# Lights.net
KiCad netlist of a schematic drawn in Altium Designer
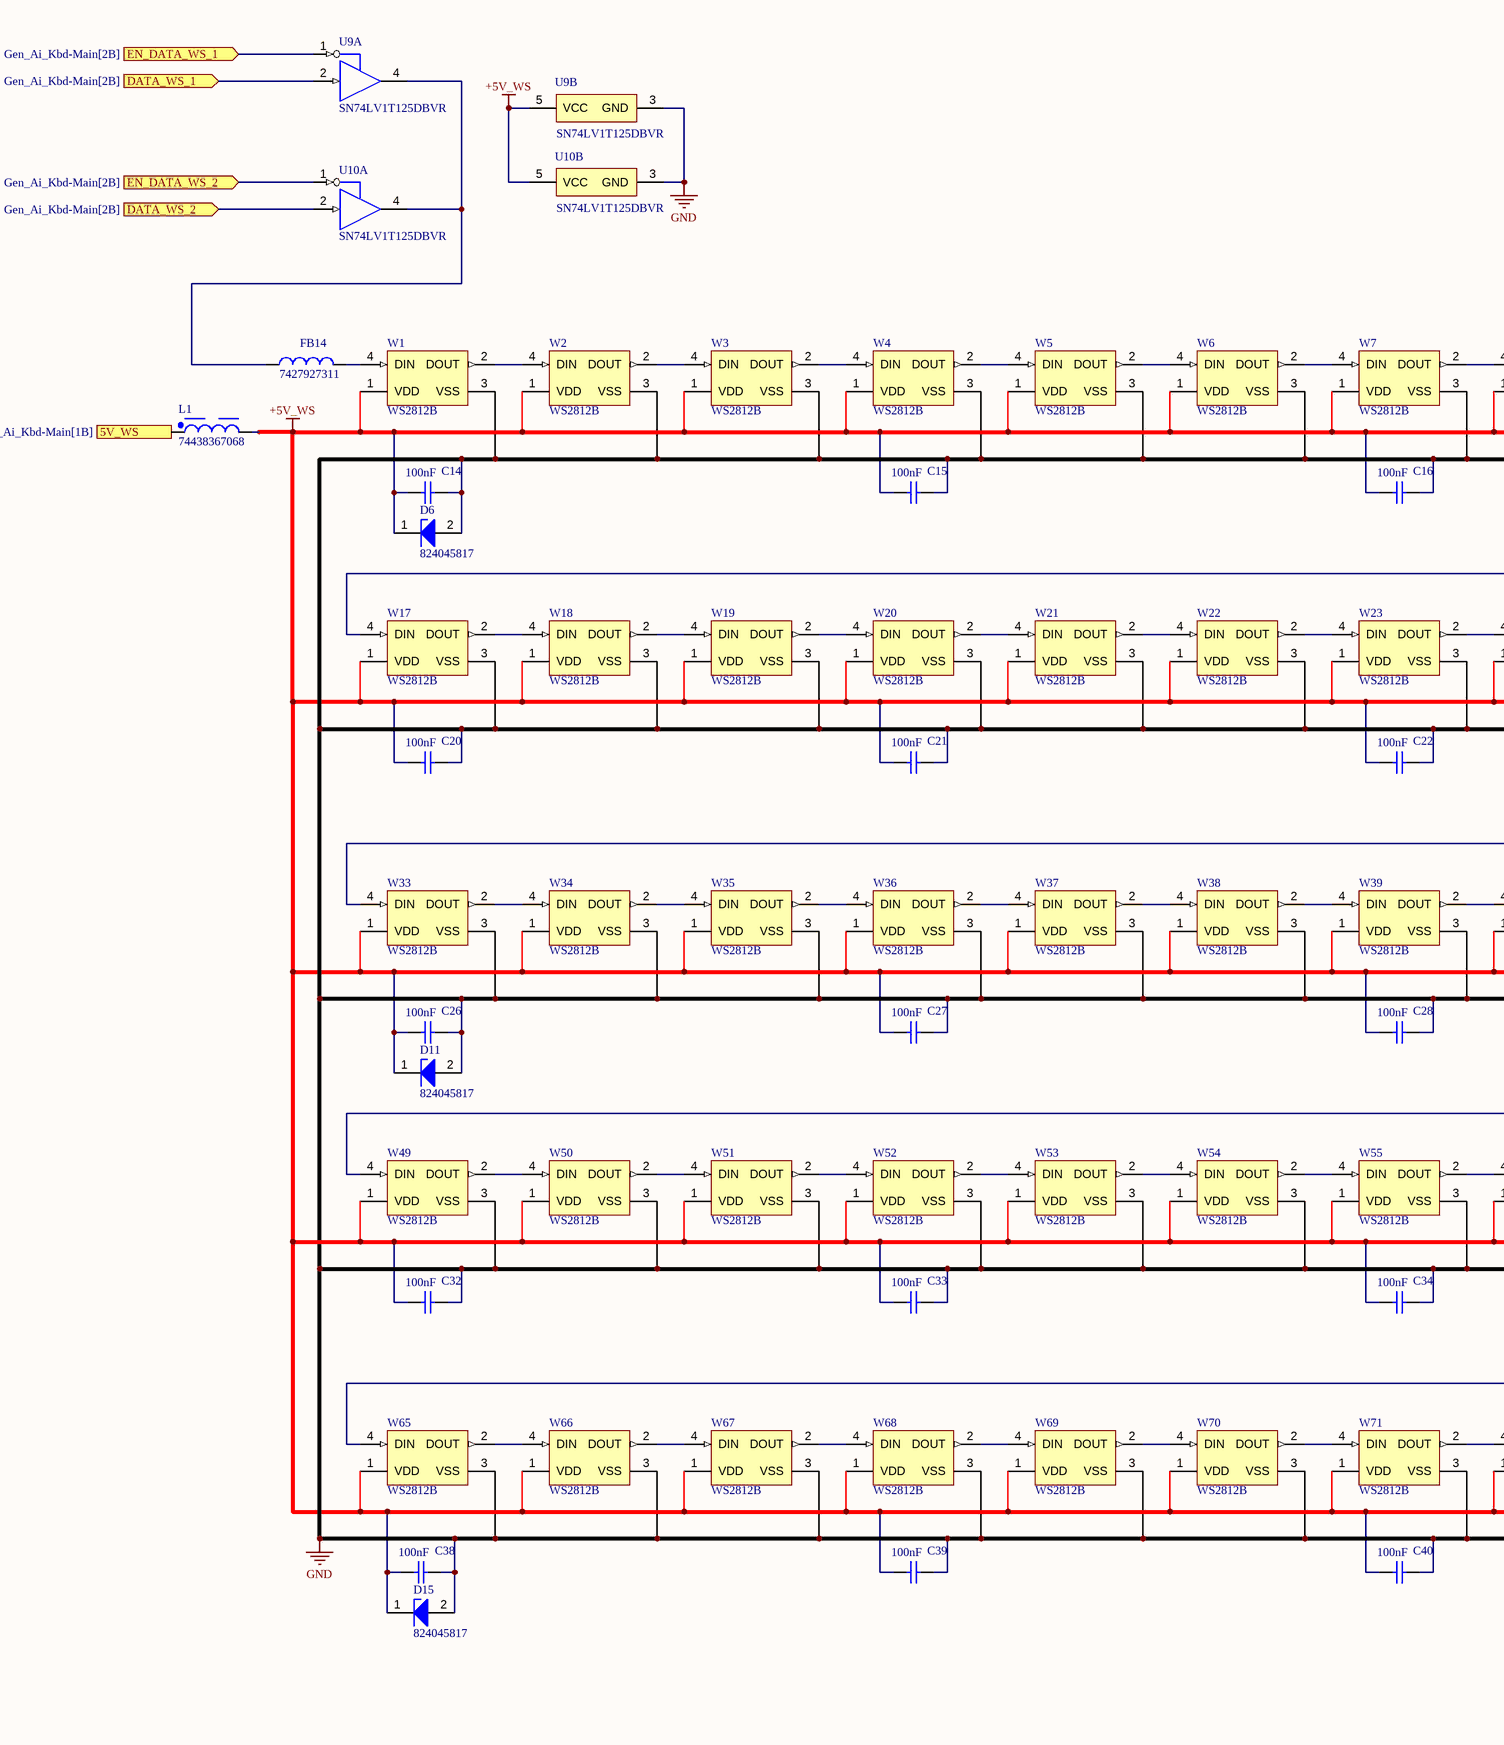
[diagram p0: Lights.SchDoc, left]
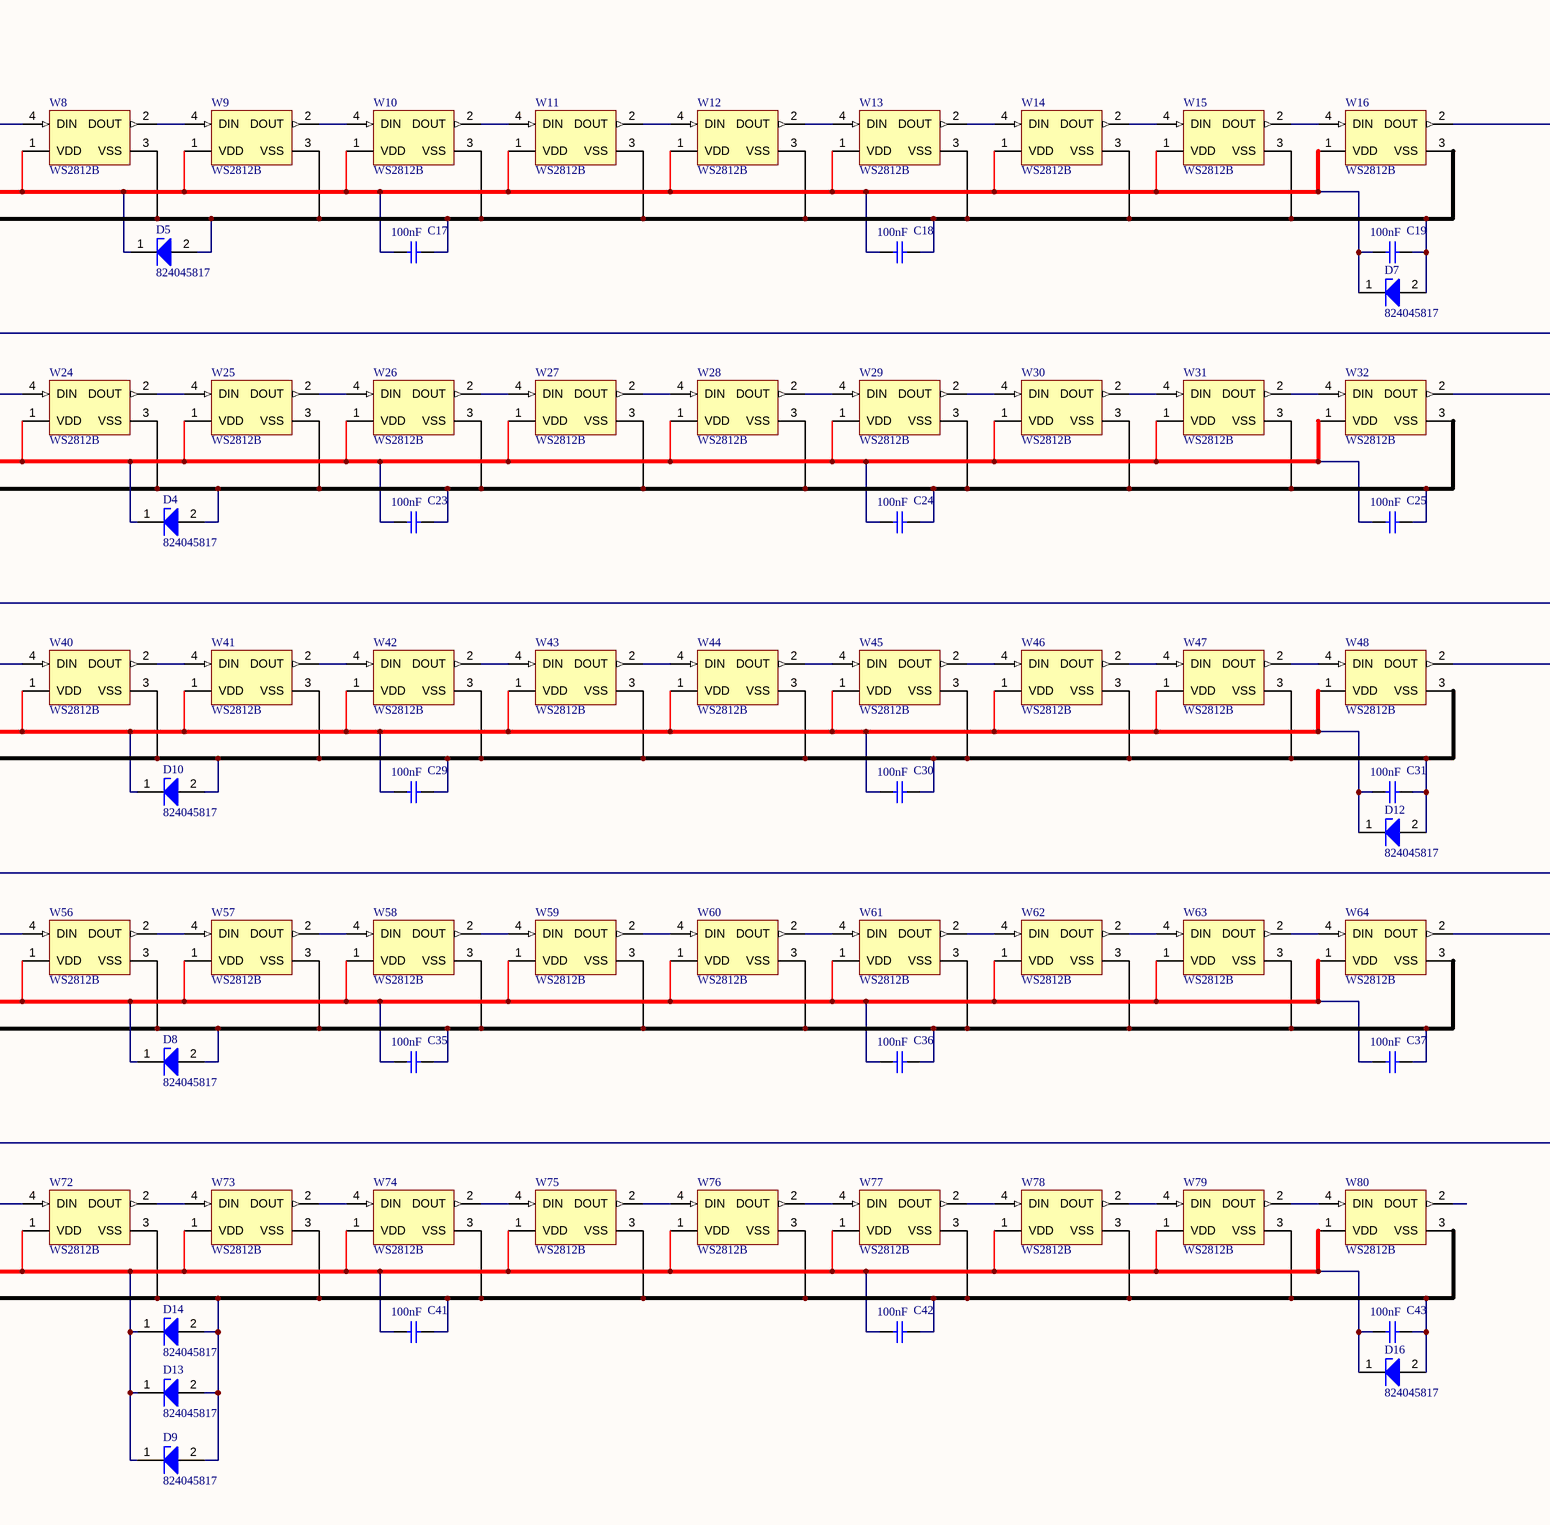
[diagram p1: Lights.SchDoc, right]

(export (version "E")
  (design (tool "Eeschema 10.0.6"))
  (components
    (comp (ref "C14")
      (value "885012205018")
      (footprint "WCAP-CSGP_0402_L1W0.5H0.5")
      (description "WCAP-CSGP Multilayer Ceramic Chip Capacitor, General Purpose, size 0402, X7R, 100nF, 10VDC")
      (fields (field (name "CAPACITANCE") "100nF") (field (name "MANUFACTURER") "Wurth Elektronik"))
      (libsource (lib "Test365") (part "885012209047R"))
    )
    (comp (ref "C15")
      (value "885012205018")
      (footprint "WCAP-CSGP_0402_L1W0.5H0.5")
      (description "WCAP-CSGP Multilayer Ceramic Chip Capacitor, General Purpose, size 0402, X7R, 100nF, 10VDC")
      (fields (field (name "CAPACITANCE") "100nF") (field (name "MANUFACTURER") "Wurth Elektronik"))
      (libsource (lib "Test365") (part "885012209047R"))
    )
    (comp (ref "C16")
      (value "885012205018")
      (footprint "WCAP-CSGP_0402_L1W0.5H0.5")
      (description "WCAP-CSGP Multilayer Ceramic Chip Capacitor, General Purpose, size 0402, X7R, 100nF, 10VDC")
      (fields (field (name "CAPACITANCE") "100nF") (field (name "MANUFACTURER") "Wurth Elektronik"))
      (libsource (lib "Test365") (part "885012209047R"))
    )
    (comp (ref "C17")
      (value "885012205018")
      (footprint "WCAP-CSGP_0402_L1W0.5H0.5")
      (description "WCAP-CSGP Multilayer Ceramic Chip Capacitor, General Purpose, size 0402, X7R, 100nF, 10VDC")
      (fields (field (name "CAPACITANCE") "100nF") (field (name "MANUFACTURER") "Wurth Elektronik"))
      (libsource (lib "Test365") (part "885012209047R"))
    )
    (comp (ref "C18")
      (value "885012205018")
      (footprint "WCAP-CSGP_0402_L1W0.5H0.5")
      (description "WCAP-CSGP Multilayer Ceramic Chip Capacitor, General Purpose, size 0402, X7R, 100nF, 10VDC")
      (fields (field (name "CAPACITANCE") "100nF") (field (name "MANUFACTURER") "Wurth Elektronik"))
      (libsource (lib "Test365") (part "885012209047R"))
    )
    (comp (ref "C19")
      (value "885012205018")
      (footprint "WCAP-CSGP_0402_L1W0.5H0.5")
      (description "WCAP-CSGP Multilayer Ceramic Chip Capacitor, General Purpose, size 0402, X7R, 100nF, 10VDC")
      (fields (field (name "CAPACITANCE") "100nF") (field (name "MANUFACTURER") "Wurth Elektronik"))
      (libsource (lib "Test365") (part "885012209047R"))
    )
    (comp (ref "C20")
      (value "885012205018")
      (footprint "WCAP-CSGP_0402_L1W0.5H0.5")
      (description "WCAP-CSGP Multilayer Ceramic Chip Capacitor, General Purpose, size 0402, X7R, 100nF, 10VDC")
      (fields (field (name "CAPACITANCE") "100nF") (field (name "MANUFACTURER") "Wurth Elektronik"))
      (libsource (lib "Test365") (part "885012209047R"))
    )
    (comp (ref "C21")
      (value "885012205018")
      (footprint "WCAP-CSGP_0402_L1W0.5H0.5")
      (description "WCAP-CSGP Multilayer Ceramic Chip Capacitor, General Purpose, size 0402, X7R, 100nF, 10VDC")
      (fields (field (name "CAPACITANCE") "100nF") (field (name "MANUFACTURER") "Wurth Elektronik"))
      (libsource (lib "Test365") (part "885012209047R"))
    )
    (comp (ref "C22")
      (value "885012205018")
      (footprint "WCAP-CSGP_0402_L1W0.5H0.5")
      (description "WCAP-CSGP Multilayer Ceramic Chip Capacitor, General Purpose, size 0402, X7R, 100nF, 10VDC")
      (fields (field (name "CAPACITANCE") "100nF") (field (name "MANUFACTURER") "Wurth Elektronik"))
      (libsource (lib "Test365") (part "885012209047R"))
    )
    (comp (ref "C23")
      (value "885012205018")
      (footprint "WCAP-CSGP_0402_L1W0.5H0.5")
      (description "WCAP-CSGP Multilayer Ceramic Chip Capacitor, General Purpose, size 0402, X7R, 100nF, 10VDC")
      (fields (field (name "CAPACITANCE") "100nF") (field (name "MANUFACTURER") "Wurth Elektronik"))
      (libsource (lib "Test365") (part "885012209047R"))
    )
    (comp (ref "C24")
      (value "885012205018")
      (footprint "WCAP-CSGP_0402_L1W0.5H0.5")
      (description "WCAP-CSGP Multilayer Ceramic Chip Capacitor, General Purpose, size 0402, X7R, 100nF, 10VDC")
      (fields (field (name "CAPACITANCE") "100nF") (field (name "MANUFACTURER") "Wurth Elektronik"))
      (libsource (lib "Test365") (part "885012209047R"))
    )
    (comp (ref "C25")
      (value "885012205018")
      (footprint "WCAP-CSGP_0402_L1W0.5H0.5")
      (description "WCAP-CSGP Multilayer Ceramic Chip Capacitor, General Purpose, size 0402, X7R, 100nF, 10VDC")
      (fields (field (name "CAPACITANCE") "100nF") (field (name "MANUFACTURER") "Wurth Elektronik"))
      (libsource (lib "Test365") (part "885012209047R"))
    )
    (comp (ref "C26")
      (value "885012205018")
      (footprint "WCAP-CSGP_0402_L1W0.5H0.5")
      (description "WCAP-CSGP Multilayer Ceramic Chip Capacitor, General Purpose, size 0402, X7R, 100nF, 10VDC")
      (fields (field (name "CAPACITANCE") "100nF") (field (name "MANUFACTURER") "Wurth Elektronik"))
      (libsource (lib "Test365") (part "885012209047R"))
    )
    (comp (ref "C27")
      (value "885012205018")
      (footprint "WCAP-CSGP_0402_L1W0.5H0.5")
      (description "WCAP-CSGP Multilayer Ceramic Chip Capacitor, General Purpose, size 0402, X7R, 100nF, 10VDC")
      (fields (field (name "CAPACITANCE") "100nF") (field (name "MANUFACTURER") "Wurth Elektronik"))
      (libsource (lib "Test365") (part "885012209047R"))
    )
    (comp (ref "C28")
      (value "885012205018")
      (footprint "WCAP-CSGP_0402_L1W0.5H0.5")
      (description "WCAP-CSGP Multilayer Ceramic Chip Capacitor, General Purpose, size 0402, X7R, 100nF, 10VDC")
      (fields (field (name "CAPACITANCE") "100nF") (field (name "MANUFACTURER") "Wurth Elektronik"))
      (libsource (lib "Test365") (part "885012209047R"))
    )
    (comp (ref "C29")
      (value "885012205018")
      (footprint "WCAP-CSGP_0402_L1W0.5H0.5")
      (description "WCAP-CSGP Multilayer Ceramic Chip Capacitor, General Purpose, size 0402, X7R, 100nF, 10VDC")
      (fields (field (name "CAPACITANCE") "100nF") (field (name "MANUFACTURER") "Wurth Elektronik"))
      (libsource (lib "Test365") (part "885012209047R"))
    )
    (comp (ref "C30")
      (value "885012205018")
      (footprint "WCAP-CSGP_0402_L1W0.5H0.5")
      (description "WCAP-CSGP Multilayer Ceramic Chip Capacitor, General Purpose, size 0402, X7R, 100nF, 10VDC")
      (fields (field (name "CAPACITANCE") "100nF") (field (name "MANUFACTURER") "Wurth Elektronik"))
      (libsource (lib "Test365") (part "885012209047R"))
    )
    (comp (ref "C31")
      (value "885012205018")
      (footprint "WCAP-CSGP_0402_L1W0.5H0.5")
      (description "WCAP-CSGP Multilayer Ceramic Chip Capacitor, General Purpose, size 0402, X7R, 100nF, 10VDC")
      (fields (field (name "CAPACITANCE") "100nF") (field (name "MANUFACTURER") "Wurth Elektronik"))
      (libsource (lib "Test365") (part "885012209047R"))
    )
    (comp (ref "C32")
      (value "885012205018")
      (footprint "WCAP-CSGP_0402_L1W0.5H0.5")
      (description "WCAP-CSGP Multilayer Ceramic Chip Capacitor, General Purpose, size 0402, X7R, 100nF, 10VDC")
      (fields (field (name "CAPACITANCE") "100nF") (field (name "MANUFACTURER") "Wurth Elektronik"))
      (libsource (lib "Test365") (part "885012209047R"))
    )
    (comp (ref "C33")
      (value "885012205018")
      (footprint "WCAP-CSGP_0402_L1W0.5H0.5")
      (description "WCAP-CSGP Multilayer Ceramic Chip Capacitor, General Purpose, size 0402, X7R, 100nF, 10VDC")
      (fields (field (name "CAPACITANCE") "100nF") (field (name "MANUFACTURER") "Wurth Elektronik"))
      (libsource (lib "Test365") (part "885012209047R"))
    )
    (comp (ref "C34")
      (value "885012205018")
      (footprint "WCAP-CSGP_0402_L1W0.5H0.5")
      (description "WCAP-CSGP Multilayer Ceramic Chip Capacitor, General Purpose, size 0402, X7R, 100nF, 10VDC")
      (fields (field (name "CAPACITANCE") "100nF") (field (name "MANUFACTURER") "Wurth Elektronik"))
      (libsource (lib "Test365") (part "885012209047R"))
    )
    (comp (ref "C35")
      (value "885012205018")
      (footprint "WCAP-CSGP_0402_L1W0.5H0.5")
      (description "WCAP-CSGP Multilayer Ceramic Chip Capacitor, General Purpose, size 0402, X7R, 100nF, 10VDC")
      (fields (field (name "CAPACITANCE") "100nF") (field (name "MANUFACTURER") "Wurth Elektronik"))
      (libsource (lib "Test365") (part "885012209047R"))
    )
    (comp (ref "C36")
      (value "885012205018")
      (footprint "WCAP-CSGP_0402_L1W0.5H0.5")
      (description "WCAP-CSGP Multilayer Ceramic Chip Capacitor, General Purpose, size 0402, X7R, 100nF, 10VDC")
      (fields (field (name "CAPACITANCE") "100nF") (field (name "MANUFACTURER") "Wurth Elektronik"))
      (libsource (lib "Test365") (part "885012209047R"))
    )
    (comp (ref "C37")
      (value "885012205018")
      (footprint "WCAP-CSGP_0402_L1W0.5H0.5")
      (description "WCAP-CSGP Multilayer Ceramic Chip Capacitor, General Purpose, size 0402, X7R, 100nF, 10VDC")
      (fields (field (name "CAPACITANCE") "100nF") (field (name "MANUFACTURER") "Wurth Elektronik"))
      (libsource (lib "Test365") (part "885012209047R"))
    )
    (comp (ref "C38")
      (value "885012205018")
      (footprint "WCAP-CSGP_0402_L1W0.5H0.5")
      (description "WCAP-CSGP Multilayer Ceramic Chip Capacitor, General Purpose, size 0402, X7R, 100nF, 10VDC")
      (fields (field (name "CAPACITANCE") "100nF") (field (name "MANUFACTURER") "Wurth Elektronik"))
      (libsource (lib "Test365") (part "885012209047R"))
    )
    (comp (ref "C39")
      (value "885012205018")
      (footprint "WCAP-CSGP_0402_L1W0.5H0.5")
      (description "WCAP-CSGP Multilayer Ceramic Chip Capacitor, General Purpose, size 0402, X7R, 100nF, 10VDC")
      (fields (field (name "CAPACITANCE") "100nF") (field (name "MANUFACTURER") "Wurth Elektronik"))
      (libsource (lib "Test365") (part "885012209047R"))
    )
    (comp (ref "C40")
      (value "885012205018")
      (footprint "WCAP-CSGP_0402_L1W0.5H0.5")
      (description "WCAP-CSGP Multilayer Ceramic Chip Capacitor, General Purpose, size 0402, X7R, 100nF, 10VDC")
      (fields (field (name "CAPACITANCE") "100nF") (field (name "MANUFACTURER") "Wurth Elektronik"))
      (libsource (lib "Test365") (part "885012209047R"))
    )
    (comp (ref "C41")
      (value "885012205018")
      (footprint "WCAP-CSGP_0402_L1W0.5H0.5")
      (description "WCAP-CSGP Multilayer Ceramic Chip Capacitor, General Purpose, size 0402, X7R, 100nF, 10VDC")
      (fields (field (name "CAPACITANCE") "100nF") (field (name "MANUFACTURER") "Wurth Elektronik"))
      (libsource (lib "Test365") (part "885012209047R"))
    )
    (comp (ref "C42")
      (value "885012205018")
      (footprint "WCAP-CSGP_0402_L1W0.5H0.5")
      (description "WCAP-CSGP Multilayer Ceramic Chip Capacitor, General Purpose, size 0402, X7R, 100nF, 10VDC")
      (fields (field (name "CAPACITANCE") "100nF") (field (name "MANUFACTURER") "Wurth Elektronik"))
      (libsource (lib "Test365") (part "885012209047R"))
    )
    (comp (ref "C43")
      (value "885012205018")
      (footprint "WCAP-CSGP_0402_L1W0.5H0.5")
      (description "WCAP-CSGP Multilayer Ceramic Chip Capacitor, General Purpose, size 0402, X7R, 100nF, 10VDC")
      (fields (field (name "CAPACITANCE") "100nF") (field (name "MANUFACTURER") "Wurth Elektronik"))
      (libsource (lib "Test365") (part "885012209047R"))
    )
    (comp (ref "D4")
      (value "824045817")
      (footprint "WE-TVS_DFN1610-2L")
      (description "824045817 Tvs Diode, Unidir, 7V, Dfn1610 Rohs Compliant: Yes")
      (libsource (lib "Altium Content Vault") (part "Diode_1 Channel_Unidirectional"))
    )
    (comp (ref "D5")
      (value "824045817")
      (footprint "WE-TVS_DFN1610-2L")
      (description "824045817 Tvs Diode, Unidir, 7V, Dfn1610 Rohs Compliant: Yes")
      (libsource (lib "Altium Content Vault") (part "Diode_1 Channel_Unidirectional"))
    )
    (comp (ref "D6")
      (value "824045817")
      (footprint "WE-TVS_DFN1610-2L")
      (description "824045817 Tvs Diode, Unidir, 7V, Dfn1610 Rohs Compliant: Yes")
      (libsource (lib "Altium Content Vault") (part "Diode_1 Channel_Unidirectional"))
    )
    (comp (ref "D7")
      (value "824045817")
      (footprint "WE-TVS_DFN1610-2L")
      (description "824045817 Tvs Diode, Unidir, 7V, Dfn1610 Rohs Compliant: Yes")
      (libsource (lib "Altium Content Vault") (part "Diode_1 Channel_Unidirectional"))
    )
    (comp (ref "D8")
      (value "824045817")
      (footprint "WE-TVS_DFN1610-2L")
      (description "824045817 Tvs Diode, Unidir, 7V, Dfn1610 Rohs Compliant: Yes")
      (libsource (lib "Altium Content Vault") (part "Diode_1 Channel_Unidirectional"))
    )
    (comp (ref "D9")
      (value "824045817")
      (footprint "WE-TVS_DFN1610-2L")
      (description "824045817 Tvs Diode, Unidir, 7V, Dfn1610 Rohs Compliant: Yes")
      (libsource (lib "Altium Content Vault") (part "Diode_1 Channel_Unidirectional"))
    )
    (comp (ref "D10")
      (value "824045817")
      (footprint "WE-TVS_DFN1610-2L")
      (description "824045817 Tvs Diode, Unidir, 7V, Dfn1610 Rohs Compliant: Yes")
      (libsource (lib "Altium Content Vault") (part "Diode_1 Channel_Unidirectional"))
    )
    (comp (ref "D11")
      (value "824045817")
      (footprint "WE-TVS_DFN1610-2L")
      (description "824045817 Tvs Diode, Unidir, 7V, Dfn1610 Rohs Compliant: Yes")
      (libsource (lib "Altium Content Vault") (part "Diode_1 Channel_Unidirectional"))
    )
    (comp (ref "D12")
      (value "824045817")
      (footprint "WE-TVS_DFN1610-2L")
      (description "824045817 Tvs Diode, Unidir, 7V, Dfn1610 Rohs Compliant: Yes")
      (libsource (lib "Altium Content Vault") (part "Diode_1 Channel_Unidirectional"))
    )
    (comp (ref "D13")
      (value "824045817")
      (footprint "WE-TVS_DFN1610-2L")
      (description "824045817 Tvs Diode, Unidir, 7V, Dfn1610 Rohs Compliant: Yes")
      (libsource (lib "Altium Content Vault") (part "Diode_1 Channel_Unidirectional"))
    )
    (comp (ref "D14")
      (value "824045817")
      (footprint "WE-TVS_DFN1610-2L")
      (description "824045817 Tvs Diode, Unidir, 7V, Dfn1610 Rohs Compliant: Yes")
      (libsource (lib "Altium Content Vault") (part "Diode_1 Channel_Unidirectional"))
    )
    (comp (ref "D15")
      (value "824045817")
      (footprint "WE-TVS_DFN1610-2L")
      (description "824045817 Tvs Diode, Unidir, 7V, Dfn1610 Rohs Compliant: Yes")
      (libsource (lib "Altium Content Vault") (part "Diode_1 Channel_Unidirectional"))
    )
    (comp (ref "D16")
      (value "824045817")
      (footprint "WE-TVS_DFN1610-2L")
      (description "824045817 Tvs Diode, Unidir, 7V, Dfn1610 Rohs Compliant: Yes")
      (libsource (lib "Altium Content Vault") (part "Diode_1 Channel_Unidirectional"))
    )
    (comp (ref "FB14")
      (value "7427927311")
      (footprint "WE-CBF_0402_L1W0.5H0.5_HC")
      (fields (field (name "TOLERANCE") "25%"))
      (libsource (lib "Altium Content Vault") (part "Ferrite"))
    )
    (comp (ref "L1")
      (value "74438367068")
      (footprint "WE-MAPI_5030")
      (description "74438367068 Power Inductor, 6.8Uh, Shielded, 5.7A Rohs Compliant: Yes")
      (libsource (lib "Altium Content Vault") (part "Inductor - 2"))
    )
    (comp (ref "U9")
      (value "SN74LV1T125DBVR")
      (footprint "DBV0005A_M")
      (description "Single Power Supply, Single BUFFER GATE w/ 3-State Output (active low enable), DBV0005A, LARGE T&R")
      (fields
        (field (name "GENERIC PART NUMBER") "SN74LV1T125")
        (field (name "MANUFACTURER") "Texas Instruments")
      )
      (libsource (lib "Altium Content Vault") (part "TI-SN74AXXXX1X125-5"))
    )
    (comp (ref "U10")
      (value "SN74LV1T125DBVR")
      (footprint "DBV0005A_M")
      (description "Single Power Supply, Single BUFFER GATE w/ 3-State Output (active low enable), DBV0005A, LARGE T&R")
      (fields
        (field (name "GENERIC PART NUMBER") "SN74LV1T125")
        (field (name "MANUFACTURER") "Texas Instruments")
      )
      (libsource (lib "Altium Content Vault") (part "TI-SN74AXXXX1X125-5"))
    )
    (comp (ref "W1")
      (value "WS2812B")
      (footprint "ADA-RGB-1655_V")
      (description "NeoPixel 5050 RGB LED with Integrated Driver Chip - 10 Pack")
      (libsource (lib "Test365") (part "ADA-RGB-1655-4"))
    )
    (comp (ref "W2")
      (value "WS2812B")
      (footprint "ADA-RGB-1655_V")
      (description "NeoPixel 5050 RGB LED with Integrated Driver Chip - 10 Pack")
      (libsource (lib "Test365") (part "ADA-RGB-1655-4"))
    )
    (comp (ref "W3")
      (value "WS2812B")
      (footprint "ADA-RGB-1655_V")
      (description "NeoPixel 5050 RGB LED with Integrated Driver Chip - 10 Pack")
      (libsource (lib "Test365") (part "ADA-RGB-1655-4"))
    )
    (comp (ref "W4")
      (value "WS2812B")
      (footprint "ADA-RGB-1655_V")
      (description "NeoPixel 5050 RGB LED with Integrated Driver Chip - 10 Pack")
      (libsource (lib "Test365") (part "ADA-RGB-1655-4"))
    )
    (comp (ref "W5")
      (value "WS2812B")
      (footprint "ADA-RGB-1655_V")
      (description "NeoPixel 5050 RGB LED with Integrated Driver Chip - 10 Pack")
      (libsource (lib "Test365") (part "ADA-RGB-1655-4"))
    )
    (comp (ref "W6")
      (value "WS2812B")
      (footprint "ADA-RGB-1655_V")
      (description "NeoPixel 5050 RGB LED with Integrated Driver Chip - 10 Pack")
      (libsource (lib "Test365") (part "ADA-RGB-1655-4"))
    )
    (comp (ref "W7")
      (value "WS2812B")
      (footprint "ADA-RGB-1655_V")
      (description "NeoPixel 5050 RGB LED with Integrated Driver Chip - 10 Pack")
      (libsource (lib "Test365") (part "ADA-RGB-1655-4"))
    )
    (comp (ref "W8")
      (value "WS2812B")
      (footprint "ADA-RGB-1655_V")
      (description "NeoPixel 5050 RGB LED with Integrated Driver Chip - 10 Pack")
      (libsource (lib "Test365") (part "ADA-RGB-1655-4"))
    )
    (comp (ref "W9")
      (value "WS2812B")
      (footprint "ADA-RGB-1655_V")
      (description "NeoPixel 5050 RGB LED with Integrated Driver Chip - 10 Pack")
      (libsource (lib "Test365") (part "ADA-RGB-1655-4"))
    )
    (comp (ref "W10")
      (value "WS2812B")
      (footprint "ADA-RGB-1655_V")
      (description "NeoPixel 5050 RGB LED with Integrated Driver Chip - 10 Pack")
      (libsource (lib "Test365") (part "ADA-RGB-1655-4"))
    )
    (comp (ref "W11")
      (value "WS2812B")
      (footprint "ADA-RGB-1655_V")
      (description "NeoPixel 5050 RGB LED with Integrated Driver Chip - 10 Pack")
      (libsource (lib "Test365") (part "ADA-RGB-1655-4"))
    )
    (comp (ref "W12")
      (value "WS2812B")
      (footprint "ADA-RGB-1655_V")
      (description "NeoPixel 5050 RGB LED with Integrated Driver Chip - 10 Pack")
      (libsource (lib "Test365") (part "ADA-RGB-1655-4"))
    )
    (comp (ref "W13")
      (value "WS2812B")
      (footprint "ADA-RGB-1655_V")
      (description "NeoPixel 5050 RGB LED with Integrated Driver Chip - 10 Pack")
      (libsource (lib "Test365") (part "ADA-RGB-1655-4"))
    )
    (comp (ref "W14")
      (value "WS2812B")
      (footprint "ADA-RGB-1655_V")
      (description "NeoPixel 5050 RGB LED with Integrated Driver Chip - 10 Pack")
      (libsource (lib "Test365") (part "ADA-RGB-1655-4"))
    )
    (comp (ref "W15")
      (value "WS2812B")
      (footprint "ADA-RGB-1655_V")
      (description "NeoPixel 5050 RGB LED with Integrated Driver Chip - 10 Pack")
      (libsource (lib "Test365") (part "ADA-RGB-1655-4"))
    )
    (comp (ref "W16")
      (value "WS2812B")
      (footprint "ADA-RGB-1655_V")
      (description "NeoPixel 5050 RGB LED with Integrated Driver Chip - 10 Pack")
      (libsource (lib "Test365") (part "ADA-RGB-1655-4"))
    )
    (comp (ref "W17")
      (value "WS2812B")
      (footprint "ADA-RGB-1655_V")
      (description "NeoPixel 5050 RGB LED with Integrated Driver Chip - 10 Pack")
      (libsource (lib "Test365") (part "ADA-RGB-1655-4"))
    )
    (comp (ref "W18")
      (value "WS2812B")
      (footprint "ADA-RGB-1655_V")
      (description "NeoPixel 5050 RGB LED with Integrated Driver Chip - 10 Pack")
      (libsource (lib "Test365") (part "ADA-RGB-1655-4"))
    )
    (comp (ref "W19")
      (value "WS2812B")
      (footprint "ADA-RGB-1655_V")
      (description "NeoPixel 5050 RGB LED with Integrated Driver Chip - 10 Pack")
      (libsource (lib "Test365") (part "ADA-RGB-1655-4"))
    )
    (comp (ref "W20")
      (value "WS2812B")
      (footprint "ADA-RGB-1655_V")
      (description "NeoPixel 5050 RGB LED with Integrated Driver Chip - 10 Pack")
      (libsource (lib "Test365") (part "ADA-RGB-1655-4"))
    )
    (comp (ref "W21")
      (value "WS2812B")
      (footprint "ADA-RGB-1655_V")
      (description "NeoPixel 5050 RGB LED with Integrated Driver Chip - 10 Pack")
      (libsource (lib "Test365") (part "ADA-RGB-1655-4"))
    )
    (comp (ref "W22")
      (value "WS2812B")
      (footprint "ADA-RGB-1655_V")
      (description "NeoPixel 5050 RGB LED with Integrated Driver Chip - 10 Pack")
      (libsource (lib "Test365") (part "ADA-RGB-1655-4"))
    )
    (comp (ref "W23")
      (value "WS2812B")
      (footprint "ADA-RGB-1655_V")
      (description "NeoPixel 5050 RGB LED with Integrated Driver Chip - 10 Pack")
      (libsource (lib "Test365") (part "ADA-RGB-1655-4"))
    )
    (comp (ref "W24")
      (value "WS2812B")
      (footprint "ADA-RGB-1655_V")
      (description "NeoPixel 5050 RGB LED with Integrated Driver Chip - 10 Pack")
      (libsource (lib "Test365") (part "ADA-RGB-1655-4"))
    )
    (comp (ref "W25")
      (value "WS2812B")
      (footprint "ADA-RGB-1655_V")
      (description "NeoPixel 5050 RGB LED with Integrated Driver Chip - 10 Pack")
      (libsource (lib "Test365") (part "ADA-RGB-1655-4"))
    )
    (comp (ref "W26")
      (value "WS2812B")
      (footprint "ADA-RGB-1655_V")
      (description "NeoPixel 5050 RGB LED with Integrated Driver Chip - 10 Pack")
      (libsource (lib "Test365") (part "ADA-RGB-1655-4"))
    )
    (comp (ref "W27")
      (value "WS2812B")
      (footprint "ADA-RGB-1655_V")
      (description "NeoPixel 5050 RGB LED with Integrated Driver Chip - 10 Pack")
      (libsource (lib "Test365") (part "ADA-RGB-1655-4"))
    )
    (comp (ref "W28")
      (value "WS2812B")
      (footprint "ADA-RGB-1655_V")
      (description "NeoPixel 5050 RGB LED with Integrated Driver Chip - 10 Pack")
      (libsource (lib "Test365") (part "ADA-RGB-1655-4"))
    )
    (comp (ref "W29")
      (value "WS2812B")
      (footprint "ADA-RGB-1655_V")
      (description "NeoPixel 5050 RGB LED with Integrated Driver Chip - 10 Pack")
      (libsource (lib "Test365") (part "ADA-RGB-1655-4"))
    )
    (comp (ref "W30")
      (value "WS2812B")
      (footprint "ADA-RGB-1655_V")
      (description "NeoPixel 5050 RGB LED with Integrated Driver Chip - 10 Pack")
      (libsource (lib "Test365") (part "ADA-RGB-1655-4"))
    )
    (comp (ref "W31")
      (value "WS2812B")
      (footprint "ADA-RGB-1655_V")
      (description "NeoPixel 5050 RGB LED with Integrated Driver Chip - 10 Pack")
      (libsource (lib "Test365") (part "ADA-RGB-1655-4"))
    )
    (comp (ref "W32")
      (value "WS2812B")
      (footprint "ADA-RGB-1655_V")
      (description "NeoPixel 5050 RGB LED with Integrated Driver Chip - 10 Pack")
      (libsource (lib "Test365") (part "ADA-RGB-1655-4"))
    )
    (comp (ref "W33")
      (value "WS2812B")
      (footprint "ADA-RGB-1655_V")
      (description "NeoPixel 5050 RGB LED with Integrated Driver Chip - 10 Pack")
      (libsource (lib "Test365") (part "ADA-RGB-1655-4"))
    )
    (comp (ref "W34")
      (value "WS2812B")
      (footprint "ADA-RGB-1655_V")
      (description "NeoPixel 5050 RGB LED with Integrated Driver Chip - 10 Pack")
      (libsource (lib "Test365") (part "ADA-RGB-1655-4"))
    )
    (comp (ref "W35")
      (value "WS2812B")
      (footprint "ADA-RGB-1655_V")
      (description "NeoPixel 5050 RGB LED with Integrated Driver Chip - 10 Pack")
      (libsource (lib "Test365") (part "ADA-RGB-1655-4"))
    )
    (comp (ref "W36")
      (value "WS2812B")
      (footprint "ADA-RGB-1655_V")
      (description "NeoPixel 5050 RGB LED with Integrated Driver Chip - 10 Pack")
      (libsource (lib "Test365") (part "ADA-RGB-1655-4"))
    )
    (comp (ref "W37")
      (value "WS2812B")
      (footprint "ADA-RGB-1655_V")
      (description "NeoPixel 5050 RGB LED with Integrated Driver Chip - 10 Pack")
      (libsource (lib "Test365") (part "ADA-RGB-1655-4"))
    )
    (comp (ref "W38")
      (value "WS2812B")
      (footprint "ADA-RGB-1655_V")
      (description "NeoPixel 5050 RGB LED with Integrated Driver Chip - 10 Pack")
      (libsource (lib "Test365") (part "ADA-RGB-1655-4"))
    )
    (comp (ref "W39")
      (value "WS2812B")
      (footprint "ADA-RGB-1655_V")
      (description "NeoPixel 5050 RGB LED with Integrated Driver Chip - 10 Pack")
      (libsource (lib "Test365") (part "ADA-RGB-1655-4"))
    )
    (comp (ref "W40")
      (value "WS2812B")
      (footprint "ADA-RGB-1655_V")
      (description "NeoPixel 5050 RGB LED with Integrated Driver Chip - 10 Pack")
      (libsource (lib "Test365") (part "ADA-RGB-1655-4"))
    )
    (comp (ref "W41")
      (value "WS2812B")
      (footprint "ADA-RGB-1655_V")
      (description "NeoPixel 5050 RGB LED with Integrated Driver Chip - 10 Pack")
      (libsource (lib "Test365") (part "ADA-RGB-1655-4"))
    )
    (comp (ref "W42")
      (value "WS2812B")
      (footprint "ADA-RGB-1655_V")
      (description "NeoPixel 5050 RGB LED with Integrated Driver Chip - 10 Pack")
      (libsource (lib "Test365") (part "ADA-RGB-1655-4"))
    )
    (comp (ref "W43")
      (value "WS2812B")
      (footprint "ADA-RGB-1655_V")
      (description "NeoPixel 5050 RGB LED with Integrated Driver Chip - 10 Pack")
      (libsource (lib "Test365") (part "ADA-RGB-1655-4"))
    )
    (comp (ref "W44")
      (value "WS2812B")
      (footprint "ADA-RGB-1655_V")
      (description "NeoPixel 5050 RGB LED with Integrated Driver Chip - 10 Pack")
      (libsource (lib "Test365") (part "ADA-RGB-1655-4"))
    )
    (comp (ref "W45")
      (value "WS2812B")
      (footprint "ADA-RGB-1655_V")
      (description "NeoPixel 5050 RGB LED with Integrated Driver Chip - 10 Pack")
      (libsource (lib "Test365") (part "ADA-RGB-1655-4"))
    )
    (comp (ref "W46")
      (value "WS2812B")
      (footprint "ADA-RGB-1655_V")
      (description "NeoPixel 5050 RGB LED with Integrated Driver Chip - 10 Pack")
      (libsource (lib "Test365") (part "ADA-RGB-1655-4"))
    )
    (comp (ref "W47")
      (value "WS2812B")
      (footprint "ADA-RGB-1655_V")
      (description "NeoPixel 5050 RGB LED with Integrated Driver Chip - 10 Pack")
      (libsource (lib "Test365") (part "ADA-RGB-1655-4"))
    )
    (comp (ref "W48")
      (value "WS2812B")
      (footprint "ADA-RGB-1655_V")
      (description "NeoPixel 5050 RGB LED with Integrated Driver Chip - 10 Pack")
      (libsource (lib "Test365") (part "ADA-RGB-1655-4"))
    )
    (comp (ref "W49")
      (value "WS2812B")
      (footprint "ADA-RGB-1655_V")
      (description "NeoPixel 5050 RGB LED with Integrated Driver Chip - 10 Pack")
      (libsource (lib "Test365") (part "ADA-RGB-1655-4"))
    )
    (comp (ref "W50")
      (value "WS2812B")
      (footprint "ADA-RGB-1655_V")
      (description "NeoPixel 5050 RGB LED with Integrated Driver Chip - 10 Pack")
      (libsource (lib "Test365") (part "ADA-RGB-1655-4"))
    )
    (comp (ref "W51")
      (value "WS2812B")
      (footprint "ADA-RGB-1655_V")
      (description "NeoPixel 5050 RGB LED with Integrated Driver Chip - 10 Pack")
      (libsource (lib "Test365") (part "ADA-RGB-1655-4"))
    )
    (comp (ref "W52")
      (value "WS2812B")
      (footprint "ADA-RGB-1655_V")
      (description "NeoPixel 5050 RGB LED with Integrated Driver Chip - 10 Pack")
      (libsource (lib "Test365") (part "ADA-RGB-1655-4"))
    )
    (comp (ref "W53")
      (value "WS2812B")
      (footprint "ADA-RGB-1655_V")
      (description "NeoPixel 5050 RGB LED with Integrated Driver Chip - 10 Pack")
      (libsource (lib "Test365") (part "ADA-RGB-1655-4"))
    )
    (comp (ref "W54")
      (value "WS2812B")
      (footprint "ADA-RGB-1655_V")
      (description "NeoPixel 5050 RGB LED with Integrated Driver Chip - 10 Pack")
      (libsource (lib "Test365") (part "ADA-RGB-1655-4"))
    )
    (comp (ref "W55")
      (value "WS2812B")
      (footprint "ADA-RGB-1655_V")
      (description "NeoPixel 5050 RGB LED with Integrated Driver Chip - 10 Pack")
      (libsource (lib "Test365") (part "ADA-RGB-1655-4"))
    )
    (comp (ref "W56")
      (value "WS2812B")
      (footprint "ADA-RGB-1655_V")
      (description "NeoPixel 5050 RGB LED with Integrated Driver Chip - 10 Pack")
      (libsource (lib "Test365") (part "ADA-RGB-1655-4"))
    )
    (comp (ref "W57")
      (value "WS2812B")
      (footprint "ADA-RGB-1655_V")
      (description "NeoPixel 5050 RGB LED with Integrated Driver Chip - 10 Pack")
      (libsource (lib "Test365") (part "ADA-RGB-1655-4"))
    )
    (comp (ref "W58")
      (value "WS2812B")
      (footprint "ADA-RGB-1655_V")
      (description "NeoPixel 5050 RGB LED with Integrated Driver Chip - 10 Pack")
      (libsource (lib "Test365") (part "ADA-RGB-1655-4"))
    )
    (comp (ref "W59")
      (value "WS2812B")
      (footprint "ADA-RGB-1655_V")
      (description "NeoPixel 5050 RGB LED with Integrated Driver Chip - 10 Pack")
      (libsource (lib "Test365") (part "ADA-RGB-1655-4"))
    )
    (comp (ref "W60")
      (value "WS2812B")
      (footprint "ADA-RGB-1655_V")
      (description "NeoPixel 5050 RGB LED with Integrated Driver Chip - 10 Pack")
      (libsource (lib "Test365") (part "ADA-RGB-1655-4"))
    )
    (comp (ref "W61")
      (value "WS2812B")
      (footprint "ADA-RGB-1655_V")
      (description "NeoPixel 5050 RGB LED with Integrated Driver Chip - 10 Pack")
      (libsource (lib "Test365") (part "ADA-RGB-1655-4"))
    )
    (comp (ref "W62")
      (value "WS2812B")
      (footprint "ADA-RGB-1655_V")
      (description "NeoPixel 5050 RGB LED with Integrated Driver Chip - 10 Pack")
      (libsource (lib "Test365") (part "ADA-RGB-1655-4"))
    )
    (comp (ref "W63")
      (value "WS2812B")
      (footprint "ADA-RGB-1655_V")
      (description "NeoPixel 5050 RGB LED with Integrated Driver Chip - 10 Pack")
      (libsource (lib "Test365") (part "ADA-RGB-1655-4"))
    )
    (comp (ref "W64")
      (value "WS2812B")
      (footprint "ADA-RGB-1655_V")
      (description "NeoPixel 5050 RGB LED with Integrated Driver Chip - 10 Pack")
      (libsource (lib "Test365") (part "ADA-RGB-1655-4"))
    )
    (comp (ref "W65")
      (value "WS2812B")
      (footprint "ADA-RGB-1655_V")
      (description "NeoPixel 5050 RGB LED with Integrated Driver Chip - 10 Pack")
      (libsource (lib "Test365") (part "ADA-RGB-1655-4"))
    )
    (comp (ref "W66")
      (value "WS2812B")
      (footprint "ADA-RGB-1655_V")
      (description "NeoPixel 5050 RGB LED with Integrated Driver Chip - 10 Pack")
      (libsource (lib "Test365") (part "ADA-RGB-1655-4"))
    )
    (comp (ref "W67")
      (value "WS2812B")
      (footprint "ADA-RGB-1655_V")
      (description "NeoPixel 5050 RGB LED with Integrated Driver Chip - 10 Pack")
      (libsource (lib "Test365") (part "ADA-RGB-1655-4"))
    )
    (comp (ref "W68")
      (value "WS2812B")
      (footprint "ADA-RGB-1655_V")
      (description "NeoPixel 5050 RGB LED with Integrated Driver Chip - 10 Pack")
      (libsource (lib "Test365") (part "ADA-RGB-1655-4"))
    )
    (comp (ref "W69")
      (value "WS2812B")
      (footprint "ADA-RGB-1655_V")
      (description "NeoPixel 5050 RGB LED with Integrated Driver Chip - 10 Pack")
      (libsource (lib "Test365") (part "ADA-RGB-1655-4"))
    )
    (comp (ref "W70")
      (value "WS2812B")
      (footprint "ADA-RGB-1655_V")
      (description "NeoPixel 5050 RGB LED with Integrated Driver Chip - 10 Pack")
      (libsource (lib "Test365") (part "ADA-RGB-1655-4"))
    )
    (comp (ref "W71")
      (value "WS2812B")
      (footprint "ADA-RGB-1655_V")
      (description "NeoPixel 5050 RGB LED with Integrated Driver Chip - 10 Pack")
      (libsource (lib "Test365") (part "ADA-RGB-1655-4"))
    )
    (comp (ref "W72")
      (value "WS2812B")
      (footprint "ADA-RGB-1655_V")
      (description "NeoPixel 5050 RGB LED with Integrated Driver Chip - 10 Pack")
      (libsource (lib "Test365") (part "ADA-RGB-1655-4"))
    )
    (comp (ref "W73")
      (value "WS2812B")
      (footprint "ADA-RGB-1655_V")
      (description "NeoPixel 5050 RGB LED with Integrated Driver Chip - 10 Pack")
      (libsource (lib "Test365") (part "ADA-RGB-1655-4"))
    )
    (comp (ref "W74")
      (value "WS2812B")
      (footprint "ADA-RGB-1655_V")
      (description "NeoPixel 5050 RGB LED with Integrated Driver Chip - 10 Pack")
      (libsource (lib "Test365") (part "ADA-RGB-1655-4"))
    )
    (comp (ref "W75")
      (value "WS2812B")
      (footprint "ADA-RGB-1655_V")
      (description "NeoPixel 5050 RGB LED with Integrated Driver Chip - 10 Pack")
      (libsource (lib "Test365") (part "ADA-RGB-1655-4"))
    )
    (comp (ref "W76")
      (value "WS2812B")
      (footprint "ADA-RGB-1655_V")
      (description "NeoPixel 5050 RGB LED with Integrated Driver Chip - 10 Pack")
      (libsource (lib "Test365") (part "ADA-RGB-1655-4"))
    )
    (comp (ref "W77")
      (value "WS2812B")
      (footprint "ADA-RGB-1655_V")
      (description "NeoPixel 5050 RGB LED with Integrated Driver Chip - 10 Pack")
      (libsource (lib "Test365") (part "ADA-RGB-1655-4"))
    )
    (comp (ref "W78")
      (value "WS2812B")
      (footprint "ADA-RGB-1655_V")
      (description "NeoPixel 5050 RGB LED with Integrated Driver Chip - 10 Pack")
      (libsource (lib "Test365") (part "ADA-RGB-1655-4"))
    )
    (comp (ref "W79")
      (value "WS2812B")
      (footprint "ADA-RGB-1655_V")
      (description "NeoPixel 5050 RGB LED with Integrated Driver Chip - 10 Pack")
      (libsource (lib "Test365") (part "ADA-RGB-1655-4"))
    )
    (comp (ref "W80")
      (value "WS2812B")
      (footprint "ADA-RGB-1655_V")
      (description "NeoPixel 5050 RGB LED with Integrated Driver Chip - 10 Pack")
      (libsource (lib "Test365") (part "ADA-RGB-1655-4"))
    )
  )
  (nets
    (net (code "1") (name "+5V_WS") (class "Default")
      (node (ref "C14") (pin "1") (pinfunction "1_1") (pintype "passive"))
      (node (ref "C15") (pin "1") (pinfunction "1_1") (pintype "passive"))
      (node (ref "C16") (pin "1") (pinfunction "1_1") (pintype "passive"))
      (node (ref "C17") (pin "1") (pinfunction "1_1") (pintype "passive"))
      (node (ref "C18") (pin "1") (pinfunction "1_1") (pintype "passive"))
      (node (ref "C19") (pin "1") (pinfunction "1_1") (pintype "passive"))
      (node (ref "C20") (pin "1") (pinfunction "1_1") (pintype "passive"))
      (node (ref "C21") (pin "1") (pinfunction "1_1") (pintype "passive"))
      (node (ref "C22") (pin "1") (pinfunction "1_1") (pintype "passive"))
      (node (ref "C23") (pin "1") (pinfunction "1_1") (pintype "passive"))
      (node (ref "C24") (pin "1") (pinfunction "1_1") (pintype "passive"))
      (node (ref "C25") (pin "1") (pinfunction "1_1") (pintype "passive"))
      (node (ref "C26") (pin "1") (pinfunction "1_1") (pintype "passive"))
      (node (ref "C27") (pin "1") (pinfunction "1_1") (pintype "passive"))
      (node (ref "C28") (pin "1") (pinfunction "1_1") (pintype "passive"))
      (node (ref "C29") (pin "1") (pinfunction "1_1") (pintype "passive"))
      (node (ref "C30") (pin "1") (pinfunction "1_1") (pintype "passive"))
      (node (ref "C31") (pin "1") (pinfunction "1_1") (pintype "passive"))
      (node (ref "C32") (pin "1") (pinfunction "1_1") (pintype "passive"))
      (node (ref "C33") (pin "1") (pinfunction "1_1") (pintype "passive"))
      (node (ref "C34") (pin "1") (pinfunction "1_1") (pintype "passive"))
      (node (ref "C35") (pin "1") (pinfunction "1_1") (pintype "passive"))
      (node (ref "C36") (pin "1") (pinfunction "1_1") (pintype "passive"))
      (node (ref "C37") (pin "1") (pinfunction "1_1") (pintype "passive"))
      (node (ref "C38") (pin "1") (pinfunction "1_1") (pintype "passive"))
      (node (ref "C39") (pin "1") (pinfunction "1_1") (pintype "passive"))
      (node (ref "C40") (pin "1") (pinfunction "1_1") (pintype "passive"))
      (node (ref "C41") (pin "1") (pinfunction "1_1") (pintype "passive"))
      (node (ref "C42") (pin "1") (pinfunction "1_1") (pintype "passive"))
      (node (ref "C43") (pin "1") (pinfunction "1_1") (pintype "passive"))
      (node (ref "D10") (pin "1") (pinfunction "I/O_1_1") (pintype "passive"))
      (node (ref "D11") (pin "1") (pinfunction "I/O_1_1") (pintype "passive"))
      (node (ref "D12") (pin "1") (pinfunction "I/O_1_1") (pintype "passive"))
      (node (ref "D13") (pin "1") (pinfunction "I/O_1_1") (pintype "passive"))
      (node (ref "D14") (pin "1") (pinfunction "I/O_1_1") (pintype "passive"))
      (node (ref "D15") (pin "1") (pinfunction "I/O_1_1") (pintype "passive"))
      (node (ref "D16") (pin "1") (pinfunction "I/O_1_1") (pintype "passive"))
      (node (ref "D4") (pin "1") (pinfunction "I/O_1_1") (pintype "passive"))
      (node (ref "D5") (pin "1") (pinfunction "I/O_1_1") (pintype "passive"))
      (node (ref "D6") (pin "1") (pinfunction "I/O_1_1") (pintype "passive"))
      (node (ref "D7") (pin "1") (pinfunction "I/O_1_1") (pintype "passive"))
      (node (ref "D8") (pin "1") (pinfunction "I/O_1_1") (pintype "passive"))
      (node (ref "D9") (pin "1") (pinfunction "I/O_1_1") (pintype "passive"))
      (node (ref "L1") (pin "2") (pinfunction "2_2") (pintype "passive"))
      (node (ref "U10") (pin "5") (pinfunction "VCC_5") (pintype "power_in"))
      (node (ref "U9") (pin "5") (pinfunction "VCC_5") (pintype "power_in"))
      (node (ref "W1") (pin "1") (pinfunction "VDD_1") (pintype "power_in"))
      (node (ref "W10") (pin "1") (pinfunction "VDD_1") (pintype "power_in"))
      (node (ref "W11") (pin "1") (pinfunction "VDD_1") (pintype "power_in"))
      (node (ref "W12") (pin "1") (pinfunction "VDD_1") (pintype "power_in"))
      (node (ref "W13") (pin "1") (pinfunction "VDD_1") (pintype "power_in"))
      (node (ref "W14") (pin "1") (pinfunction "VDD_1") (pintype "power_in"))
      (node (ref "W15") (pin "1") (pinfunction "VDD_1") (pintype "power_in"))
      (node (ref "W16") (pin "1") (pinfunction "VDD_1") (pintype "power_in"))
      (node (ref "W17") (pin "1") (pinfunction "VDD_1") (pintype "power_in"))
      (node (ref "W18") (pin "1") (pinfunction "VDD_1") (pintype "power_in"))
      (node (ref "W19") (pin "1") (pinfunction "VDD_1") (pintype "power_in"))
      (node (ref "W2") (pin "1") (pinfunction "VDD_1") (pintype "power_in"))
      (node (ref "W20") (pin "1") (pinfunction "VDD_1") (pintype "power_in"))
      (node (ref "W21") (pin "1") (pinfunction "VDD_1") (pintype "power_in"))
      (node (ref "W22") (pin "1") (pinfunction "VDD_1") (pintype "power_in"))
      (node (ref "W23") (pin "1") (pinfunction "VDD_1") (pintype "power_in"))
      (node (ref "W24") (pin "1") (pinfunction "VDD_1") (pintype "power_in"))
      (node (ref "W25") (pin "1") (pinfunction "VDD_1") (pintype "power_in"))
      (node (ref "W26") (pin "1") (pinfunction "VDD_1") (pintype "power_in"))
      (node (ref "W27") (pin "1") (pinfunction "VDD_1") (pintype "power_in"))
      (node (ref "W28") (pin "1") (pinfunction "VDD_1") (pintype "power_in"))
      (node (ref "W29") (pin "1") (pinfunction "VDD_1") (pintype "power_in"))
      (node (ref "W3") (pin "1") (pinfunction "VDD_1") (pintype "power_in"))
      (node (ref "W30") (pin "1") (pinfunction "VDD_1") (pintype "power_in"))
      (node (ref "W31") (pin "1") (pinfunction "VDD_1") (pintype "power_in"))
      (node (ref "W32") (pin "1") (pinfunction "VDD_1") (pintype "power_in"))
      (node (ref "W33") (pin "1") (pinfunction "VDD_1") (pintype "power_in"))
      (node (ref "W34") (pin "1") (pinfunction "VDD_1") (pintype "power_in"))
      (node (ref "W35") (pin "1") (pinfunction "VDD_1") (pintype "power_in"))
      (node (ref "W36") (pin "1") (pinfunction "VDD_1") (pintype "power_in"))
      (node (ref "W37") (pin "1") (pinfunction "VDD_1") (pintype "power_in"))
      (node (ref "W38") (pin "1") (pinfunction "VDD_1") (pintype "power_in"))
      (node (ref "W39") (pin "1") (pinfunction "VDD_1") (pintype "power_in"))
      (node (ref "W4") (pin "1") (pinfunction "VDD_1") (pintype "power_in"))
      (node (ref "W40") (pin "1") (pinfunction "VDD_1") (pintype "power_in"))
      (node (ref "W41") (pin "1") (pinfunction "VDD_1") (pintype "power_in"))
      (node (ref "W42") (pin "1") (pinfunction "VDD_1") (pintype "power_in"))
      (node (ref "W43") (pin "1") (pinfunction "VDD_1") (pintype "power_in"))
      (node (ref "W44") (pin "1") (pinfunction "VDD_1") (pintype "power_in"))
      (node (ref "W45") (pin "1") (pinfunction "VDD_1") (pintype "power_in"))
      (node (ref "W46") (pin "1") (pinfunction "VDD_1") (pintype "power_in"))
      (node (ref "W47") (pin "1") (pinfunction "VDD_1") (pintype "power_in"))
      (node (ref "W48") (pin "1") (pinfunction "VDD_1") (pintype "power_in"))
      (node (ref "W49") (pin "1") (pinfunction "VDD_1") (pintype "power_in"))
      (node (ref "W5") (pin "1") (pinfunction "VDD_1") (pintype "power_in"))
      (node (ref "W50") (pin "1") (pinfunction "VDD_1") (pintype "power_in"))
      (node (ref "W51") (pin "1") (pinfunction "VDD_1") (pintype "power_in"))
      (node (ref "W52") (pin "1") (pinfunction "VDD_1") (pintype "power_in"))
      (node (ref "W53") (pin "1") (pinfunction "VDD_1") (pintype "power_in"))
      (node (ref "W54") (pin "1") (pinfunction "VDD_1") (pintype "power_in"))
      (node (ref "W55") (pin "1") (pinfunction "VDD_1") (pintype "power_in"))
      (node (ref "W56") (pin "1") (pinfunction "VDD_1") (pintype "power_in"))
      (node (ref "W57") (pin "1") (pinfunction "VDD_1") (pintype "power_in"))
      (node (ref "W58") (pin "1") (pinfunction "VDD_1") (pintype "power_in"))
      (node (ref "W59") (pin "1") (pinfunction "VDD_1") (pintype "power_in"))
      (node (ref "W6") (pin "1") (pinfunction "VDD_1") (pintype "power_in"))
      (node (ref "W60") (pin "1") (pinfunction "VDD_1") (pintype "power_in"))
      (node (ref "W61") (pin "1") (pinfunction "VDD_1") (pintype "power_in"))
      (node (ref "W62") (pin "1") (pinfunction "VDD_1") (pintype "power_in"))
      (node (ref "W63") (pin "1") (pinfunction "VDD_1") (pintype "power_in"))
      (node (ref "W64") (pin "1") (pinfunction "VDD_1") (pintype "power_in"))
      (node (ref "W65") (pin "1") (pinfunction "VDD_1") (pintype "power_in"))
      (node (ref "W66") (pin "1") (pinfunction "VDD_1") (pintype "power_in"))
      (node (ref "W67") (pin "1") (pinfunction "VDD_1") (pintype "power_in"))
      (node (ref "W68") (pin "1") (pinfunction "VDD_1") (pintype "power_in"))
      (node (ref "W69") (pin "1") (pinfunction "VDD_1") (pintype "power_in"))
      (node (ref "W7") (pin "1") (pinfunction "VDD_1") (pintype "power_in"))
      (node (ref "W70") (pin "1") (pinfunction "VDD_1") (pintype "power_in"))
      (node (ref "W71") (pin "1") (pinfunction "VDD_1") (pintype "power_in"))
      (node (ref "W72") (pin "1") (pinfunction "VDD_1") (pintype "power_in"))
      (node (ref "W73") (pin "1") (pinfunction "VDD_1") (pintype "power_in"))
      (node (ref "W74") (pin "1") (pinfunction "VDD_1") (pintype "power_in"))
      (node (ref "W75") (pin "1") (pinfunction "VDD_1") (pintype "power_in"))
      (node (ref "W76") (pin "1") (pinfunction "VDD_1") (pintype "power_in"))
      (node (ref "W77") (pin "1") (pinfunction "VDD_1") (pintype "power_in"))
      (node (ref "W78") (pin "1") (pinfunction "VDD_1") (pintype "power_in"))
      (node (ref "W79") (pin "1") (pinfunction "VDD_1") (pintype "power_in"))
      (node (ref "W8") (pin "1") (pinfunction "VDD_1") (pintype "power_in"))
      (node (ref "W80") (pin "1") (pinfunction "VDD_1") (pintype "power_in"))
      (node (ref "W9") (pin "1") (pinfunction "VDD_1") (pintype "power_in"))
    )
    (net (code "2") (name "/5V_WS") (class "Default")
      (node (ref "L1") (pin "1") (pinfunction "1_1") (pintype "passive"))
    )
    (net (code "3") (name "/DATA_WS_1") (class "Default")
      (node (ref "U9") (pin "2") (pinfunction "A_2") (pintype "input"))
    )
    (net (code "4") (name "/DATA_WS_2") (class "Default")
      (node (ref "U10") (pin "2") (pinfunction "A_2") (pintype "input"))
    )
    (net (code "5") (name "/EN_DATA_WS_1") (class "Default")
      (node (ref "U9") (pin "1") (pinfunction "~{OE}_1") (pintype "input"))
    )
    (net (code "6") (name "/EN_DATA_WS_2") (class "Default")
      (node (ref "U10") (pin "1") (pinfunction "~{OE}_1") (pintype "input"))
    )
    (net (code "7") (name "GND") (class "Default")
      (node (ref "C14") (pin "2") (pinfunction "2_2") (pintype "passive"))
      (node (ref "C15") (pin "2") (pinfunction "2_2") (pintype "passive"))
      (node (ref "C16") (pin "2") (pinfunction "2_2") (pintype "passive"))
      (node (ref "C17") (pin "2") (pinfunction "2_2") (pintype "passive"))
      (node (ref "C18") (pin "2") (pinfunction "2_2") (pintype "passive"))
      (node (ref "C19") (pin "2") (pinfunction "2_2") (pintype "passive"))
      (node (ref "C20") (pin "2") (pinfunction "2_2") (pintype "passive"))
      (node (ref "C21") (pin "2") (pinfunction "2_2") (pintype "passive"))
      (node (ref "C22") (pin "2") (pinfunction "2_2") (pintype "passive"))
      (node (ref "C23") (pin "2") (pinfunction "2_2") (pintype "passive"))
      (node (ref "C24") (pin "2") (pinfunction "2_2") (pintype "passive"))
      (node (ref "C25") (pin "2") (pinfunction "2_2") (pintype "passive"))
      (node (ref "C26") (pin "2") (pinfunction "2_2") (pintype "passive"))
      (node (ref "C27") (pin "2") (pinfunction "2_2") (pintype "passive"))
      (node (ref "C28") (pin "2") (pinfunction "2_2") (pintype "passive"))
      (node (ref "C29") (pin "2") (pinfunction "2_2") (pintype "passive"))
      (node (ref "C30") (pin "2") (pinfunction "2_2") (pintype "passive"))
      (node (ref "C31") (pin "2") (pinfunction "2_2") (pintype "passive"))
      (node (ref "C32") (pin "2") (pinfunction "2_2") (pintype "passive"))
      (node (ref "C33") (pin "2") (pinfunction "2_2") (pintype "passive"))
      (node (ref "C34") (pin "2") (pinfunction "2_2") (pintype "passive"))
      (node (ref "C35") (pin "2") (pinfunction "2_2") (pintype "passive"))
      (node (ref "C36") (pin "2") (pinfunction "2_2") (pintype "passive"))
      (node (ref "C37") (pin "2") (pinfunction "2_2") (pintype "passive"))
      (node (ref "C38") (pin "2") (pinfunction "2_2") (pintype "passive"))
      (node (ref "C39") (pin "2") (pinfunction "2_2") (pintype "passive"))
      (node (ref "C40") (pin "2") (pinfunction "2_2") (pintype "passive"))
      (node (ref "C41") (pin "2") (pinfunction "2_2") (pintype "passive"))
      (node (ref "C42") (pin "2") (pinfunction "2_2") (pintype "passive"))
      (node (ref "C43") (pin "2") (pinfunction "2_2") (pintype "passive"))
      (node (ref "D10") (pin "2") (pinfunction "GND_2") (pintype "passive"))
      (node (ref "D11") (pin "2") (pinfunction "GND_2") (pintype "passive"))
      (node (ref "D12") (pin "2") (pinfunction "GND_2") (pintype "passive"))
      (node (ref "D13") (pin "2") (pinfunction "GND_2") (pintype "passive"))
      (node (ref "D14") (pin "2") (pinfunction "GND_2") (pintype "passive"))
      (node (ref "D15") (pin "2") (pinfunction "GND_2") (pintype "passive"))
      (node (ref "D16") (pin "2") (pinfunction "GND_2") (pintype "passive"))
      (node (ref "D4") (pin "2") (pinfunction "GND_2") (pintype "passive"))
      (node (ref "D5") (pin "2") (pinfunction "GND_2") (pintype "passive"))
      (node (ref "D6") (pin "2") (pinfunction "GND_2") (pintype "passive"))
      (node (ref "D7") (pin "2") (pinfunction "GND_2") (pintype "passive"))
      (node (ref "D8") (pin "2") (pinfunction "GND_2") (pintype "passive"))
      (node (ref "D9") (pin "2") (pinfunction "GND_2") (pintype "passive"))
      (node (ref "U10") (pin "3") (pinfunction "GND_3") (pintype "power_in"))
      (node (ref "U9") (pin "3") (pinfunction "GND_3") (pintype "power_in"))
      (node (ref "W1") (pin "3") (pinfunction "VSS_3") (pintype "power_in"))
      (node (ref "W10") (pin "3") (pinfunction "VSS_3") (pintype "power_in"))
      (node (ref "W11") (pin "3") (pinfunction "VSS_3") (pintype "power_in"))
      (node (ref "W12") (pin "3") (pinfunction "VSS_3") (pintype "power_in"))
      (node (ref "W13") (pin "3") (pinfunction "VSS_3") (pintype "power_in"))
      (node (ref "W14") (pin "3") (pinfunction "VSS_3") (pintype "power_in"))
      (node (ref "W15") (pin "3") (pinfunction "VSS_3") (pintype "power_in"))
      (node (ref "W16") (pin "3") (pinfunction "VSS_3") (pintype "power_in"))
      (node (ref "W17") (pin "3") (pinfunction "VSS_3") (pintype "power_in"))
      (node (ref "W18") (pin "3") (pinfunction "VSS_3") (pintype "power_in"))
      (node (ref "W19") (pin "3") (pinfunction "VSS_3") (pintype "power_in"))
      (node (ref "W2") (pin "3") (pinfunction "VSS_3") (pintype "power_in"))
      (node (ref "W20") (pin "3") (pinfunction "VSS_3") (pintype "power_in"))
      (node (ref "W21") (pin "3") (pinfunction "VSS_3") (pintype "power_in"))
      (node (ref "W22") (pin "3") (pinfunction "VSS_3") (pintype "power_in"))
      (node (ref "W23") (pin "3") (pinfunction "VSS_3") (pintype "power_in"))
      (node (ref "W24") (pin "3") (pinfunction "VSS_3") (pintype "power_in"))
      (node (ref "W25") (pin "3") (pinfunction "VSS_3") (pintype "power_in"))
      (node (ref "W26") (pin "3") (pinfunction "VSS_3") (pintype "power_in"))
      (node (ref "W27") (pin "3") (pinfunction "VSS_3") (pintype "power_in"))
      (node (ref "W28") (pin "3") (pinfunction "VSS_3") (pintype "power_in"))
      (node (ref "W29") (pin "3") (pinfunction "VSS_3") (pintype "power_in"))
      (node (ref "W3") (pin "3") (pinfunction "VSS_3") (pintype "power_in"))
      (node (ref "W30") (pin "3") (pinfunction "VSS_3") (pintype "power_in"))
      (node (ref "W31") (pin "3") (pinfunction "VSS_3") (pintype "power_in"))
      (node (ref "W32") (pin "3") (pinfunction "VSS_3") (pintype "power_in"))
      (node (ref "W33") (pin "3") (pinfunction "VSS_3") (pintype "power_in"))
      (node (ref "W34") (pin "3") (pinfunction "VSS_3") (pintype "power_in"))
      (node (ref "W35") (pin "3") (pinfunction "VSS_3") (pintype "power_in"))
      (node (ref "W36") (pin "3") (pinfunction "VSS_3") (pintype "power_in"))
      (node (ref "W37") (pin "3") (pinfunction "VSS_3") (pintype "power_in"))
      (node (ref "W38") (pin "3") (pinfunction "VSS_3") (pintype "power_in"))
      (node (ref "W39") (pin "3") (pinfunction "VSS_3") (pintype "power_in"))
      (node (ref "W4") (pin "3") (pinfunction "VSS_3") (pintype "power_in"))
      (node (ref "W40") (pin "3") (pinfunction "VSS_3") (pintype "power_in"))
      (node (ref "W41") (pin "3") (pinfunction "VSS_3") (pintype "power_in"))
      (node (ref "W42") (pin "3") (pinfunction "VSS_3") (pintype "power_in"))
      (node (ref "W43") (pin "3") (pinfunction "VSS_3") (pintype "power_in"))
      (node (ref "W44") (pin "3") (pinfunction "VSS_3") (pintype "power_in"))
      (node (ref "W45") (pin "3") (pinfunction "VSS_3") (pintype "power_in"))
      (node (ref "W46") (pin "3") (pinfunction "VSS_3") (pintype "power_in"))
      (node (ref "W47") (pin "3") (pinfunction "VSS_3") (pintype "power_in"))
      (node (ref "W48") (pin "3") (pinfunction "VSS_3") (pintype "power_in"))
      (node (ref "W49") (pin "3") (pinfunction "VSS_3") (pintype "power_in"))
      (node (ref "W5") (pin "3") (pinfunction "VSS_3") (pintype "power_in"))
      (node (ref "W50") (pin "3") (pinfunction "VSS_3") (pintype "power_in"))
      (node (ref "W51") (pin "3") (pinfunction "VSS_3") (pintype "power_in"))
      (node (ref "W52") (pin "3") (pinfunction "VSS_3") (pintype "power_in"))
      (node (ref "W53") (pin "3") (pinfunction "VSS_3") (pintype "power_in"))
      (node (ref "W54") (pin "3") (pinfunction "VSS_3") (pintype "power_in"))
      (node (ref "W55") (pin "3") (pinfunction "VSS_3") (pintype "power_in"))
      (node (ref "W56") (pin "3") (pinfunction "VSS_3") (pintype "power_in"))
      (node (ref "W57") (pin "3") (pinfunction "VSS_3") (pintype "power_in"))
      (node (ref "W58") (pin "3") (pinfunction "VSS_3") (pintype "power_in"))
      (node (ref "W59") (pin "3") (pinfunction "VSS_3") (pintype "power_in"))
      (node (ref "W6") (pin "3") (pinfunction "VSS_3") (pintype "power_in"))
      (node (ref "W60") (pin "3") (pinfunction "VSS_3") (pintype "power_in"))
      (node (ref "W61") (pin "3") (pinfunction "VSS_3") (pintype "power_in"))
      (node (ref "W62") (pin "3") (pinfunction "VSS_3") (pintype "power_in"))
      (node (ref "W63") (pin "3") (pinfunction "VSS_3") (pintype "power_in"))
      (node (ref "W64") (pin "3") (pinfunction "VSS_3") (pintype "power_in"))
      (node (ref "W65") (pin "3") (pinfunction "VSS_3") (pintype "power_in"))
      (node (ref "W66") (pin "3") (pinfunction "VSS_3") (pintype "power_in"))
      (node (ref "W67") (pin "3") (pinfunction "VSS_3") (pintype "power_in"))
      (node (ref "W68") (pin "3") (pinfunction "VSS_3") (pintype "power_in"))
      (node (ref "W69") (pin "3") (pinfunction "VSS_3") (pintype "power_in"))
      (node (ref "W7") (pin "3") (pinfunction "VSS_3") (pintype "power_in"))
      (node (ref "W70") (pin "3") (pinfunction "VSS_3") (pintype "power_in"))
      (node (ref "W71") (pin "3") (pinfunction "VSS_3") (pintype "power_in"))
      (node (ref "W72") (pin "3") (pinfunction "VSS_3") (pintype "power_in"))
      (node (ref "W73") (pin "3") (pinfunction "VSS_3") (pintype "power_in"))
      (node (ref "W74") (pin "3") (pinfunction "VSS_3") (pintype "power_in"))
      (node (ref "W75") (pin "3") (pinfunction "VSS_3") (pintype "power_in"))
      (node (ref "W76") (pin "3") (pinfunction "VSS_3") (pintype "power_in"))
      (node (ref "W77") (pin "3") (pinfunction "VSS_3") (pintype "power_in"))
      (node (ref "W78") (pin "3") (pinfunction "VSS_3") (pintype "power_in"))
      (node (ref "W79") (pin "3") (pinfunction "VSS_3") (pintype "power_in"))
      (node (ref "W8") (pin "3") (pinfunction "VSS_3") (pintype "power_in"))
      (node (ref "W80") (pin "3") (pinfunction "VSS_3") (pintype "power_in"))
      (node (ref "W9") (pin "3") (pinfunction "VSS_3") (pintype "power_in"))
    )
    (net (code "8") (name "Net-(U10A-Y)") (class "Default")
      (node (ref "FB14") (pin "1") (pinfunction "1_1") (pintype "passive"))
      (node (ref "U10") (pin "4") (pinfunction "Y_4") (pintype "tri_state"))
      (node (ref "U9") (pin "4") (pinfunction "Y_4") (pintype "tri_state"))
    )
    (net (code "9") (name "Net-(W1-DIN)") (class "Default")
      (node (ref "FB14") (pin "2") (pinfunction "2_2") (pintype "passive"))
      (node (ref "W1") (pin "4") (pinfunction "DIN_4") (pintype "input"))
    )
    (net (code "10") (name "Net-(W1-DOUT)") (class "Default")
      (node (ref "W1") (pin "2") (pinfunction "DOUT_2") (pintype "output"))
      (node (ref "W2") (pin "4") (pinfunction "DIN_4") (pintype "input"))
    )
    (net (code "11") (name "Net-(W2-DOUT)") (class "Default")
      (node (ref "W2") (pin "2") (pinfunction "DOUT_2") (pintype "output"))
      (node (ref "W3") (pin "4") (pinfunction "DIN_4") (pintype "input"))
    )
    (net (code "12") (name "Net-(W3-DOUT)") (class "Default")
      (node (ref "W3") (pin "2") (pinfunction "DOUT_2") (pintype "output"))
      (node (ref "W4") (pin "4") (pinfunction "DIN_4") (pintype "input"))
    )
    (net (code "13") (name "Net-(W4-DOUT)") (class "Default")
      (node (ref "W4") (pin "2") (pinfunction "DOUT_2") (pintype "output"))
      (node (ref "W5") (pin "4") (pinfunction "DIN_4") (pintype "input"))
    )
    (net (code "14") (name "Net-(W5-DOUT)") (class "Default")
      (node (ref "W5") (pin "2") (pinfunction "DOUT_2") (pintype "output"))
      (node (ref "W6") (pin "4") (pinfunction "DIN_4") (pintype "input"))
    )
    (net (code "15") (name "Net-(W6-DOUT)") (class "Default")
      (node (ref "W6") (pin "2") (pinfunction "DOUT_2") (pintype "output"))
      (node (ref "W7") (pin "4") (pinfunction "DIN_4") (pintype "input"))
    )
    (net (code "16") (name "Net-(W7-DOUT)") (class "Default")
      (node (ref "W7") (pin "2") (pinfunction "DOUT_2") (pintype "output"))
      (node (ref "W8") (pin "4") (pinfunction "DIN_4") (pintype "input"))
    )
    (net (code "17") (name "Net-(W8-DOUT)") (class "Default")
      (node (ref "W8") (pin "2") (pinfunction "DOUT_2") (pintype "output"))
      (node (ref "W9") (pin "4") (pinfunction "DIN_4") (pintype "input"))
    )
    (net (code "18") (name "Net-(W10-DIN)") (class "Default")
      (node (ref "W10") (pin "4") (pinfunction "DIN_4") (pintype "input"))
      (node (ref "W9") (pin "2") (pinfunction "DOUT_2") (pintype "output"))
    )
    (net (code "19") (name "Net-(W10-DOUT)") (class "Default")
      (node (ref "W10") (pin "2") (pinfunction "DOUT_2") (pintype "output"))
      (node (ref "W11") (pin "4") (pinfunction "DIN_4") (pintype "input"))
    )
    (net (code "20") (name "Net-(W11-DOUT)") (class "Default")
      (node (ref "W11") (pin "2") (pinfunction "DOUT_2") (pintype "output"))
      (node (ref "W12") (pin "4") (pinfunction "DIN_4") (pintype "input"))
    )
    (net (code "21") (name "Net-(W12-DOUT)") (class "Default")
      (node (ref "W12") (pin "2") (pinfunction "DOUT_2") (pintype "output"))
      (node (ref "W13") (pin "4") (pinfunction "DIN_4") (pintype "input"))
    )
    (net (code "22") (name "Net-(W13-DOUT)") (class "Default")
      (node (ref "W13") (pin "2") (pinfunction "DOUT_2") (pintype "output"))
      (node (ref "W14") (pin "4") (pinfunction "DIN_4") (pintype "input"))
    )
    (net (code "23") (name "Net-(W14-DOUT)") (class "Default")
      (node (ref "W14") (pin "2") (pinfunction "DOUT_2") (pintype "output"))
      (node (ref "W15") (pin "4") (pinfunction "DIN_4") (pintype "input"))
    )
    (net (code "24") (name "Net-(W15-DOUT)") (class "Default")
      (node (ref "W15") (pin "2") (pinfunction "DOUT_2") (pintype "output"))
      (node (ref "W16") (pin "4") (pinfunction "DIN_4") (pintype "input"))
    )
    (net (code "25") (name "Net-(W16-DOUT)") (class "Default")
      (node (ref "W16") (pin "2") (pinfunction "DOUT_2") (pintype "output"))
      (node (ref "W17") (pin "4") (pinfunction "DIN_4") (pintype "input"))
    )
    (net (code "26") (name "Net-(W17-DOUT)") (class "Default")
      (node (ref "W17") (pin "2") (pinfunction "DOUT_2") (pintype "output"))
      (node (ref "W18") (pin "4") (pinfunction "DIN_4") (pintype "input"))
    )
    (net (code "27") (name "Net-(W18-DOUT)") (class "Default")
      (node (ref "W18") (pin "2") (pinfunction "DOUT_2") (pintype "output"))
      (node (ref "W19") (pin "4") (pinfunction "DIN_4") (pintype "input"))
    )
    (net (code "28") (name "Net-(W19-DOUT)") (class "Default")
      (node (ref "W19") (pin "2") (pinfunction "DOUT_2") (pintype "output"))
      (node (ref "W20") (pin "4") (pinfunction "DIN_4") (pintype "input"))
    )
    (net (code "29") (name "Net-(W20-DOUT)") (class "Default")
      (node (ref "W20") (pin "2") (pinfunction "DOUT_2") (pintype "output"))
      (node (ref "W21") (pin "4") (pinfunction "DIN_4") (pintype "input"))
    )
    (net (code "30") (name "Net-(W21-DOUT)") (class "Default")
      (node (ref "W21") (pin "2") (pinfunction "DOUT_2") (pintype "output"))
      (node (ref "W22") (pin "4") (pinfunction "DIN_4") (pintype "input"))
    )
    (net (code "31") (name "Net-(W22-DOUT)") (class "Default")
      (node (ref "W22") (pin "2") (pinfunction "DOUT_2") (pintype "output"))
      (node (ref "W23") (pin "4") (pinfunction "DIN_4") (pintype "input"))
    )
    (net (code "32") (name "Net-(W23-DOUT)") (class "Default")
      (node (ref "W23") (pin "2") (pinfunction "DOUT_2") (pintype "output"))
      (node (ref "W24") (pin "4") (pinfunction "DIN_4") (pintype "input"))
    )
    (net (code "33") (name "Net-(W24-DOUT)") (class "Default")
      (node (ref "W24") (pin "2") (pinfunction "DOUT_2") (pintype "output"))
      (node (ref "W25") (pin "4") (pinfunction "DIN_4") (pintype "input"))
    )
    (net (code "34") (name "Net-(W25-DOUT)") (class "Default")
      (node (ref "W25") (pin "2") (pinfunction "DOUT_2") (pintype "output"))
      (node (ref "W26") (pin "4") (pinfunction "DIN_4") (pintype "input"))
    )
    (net (code "35") (name "Net-(W26-DOUT)") (class "Default")
      (node (ref "W26") (pin "2") (pinfunction "DOUT_2") (pintype "output"))
      (node (ref "W27") (pin "4") (pinfunction "DIN_4") (pintype "input"))
    )
    (net (code "36") (name "Net-(W27-DOUT)") (class "Default")
      (node (ref "W27") (pin "2") (pinfunction "DOUT_2") (pintype "output"))
      (node (ref "W28") (pin "4") (pinfunction "DIN_4") (pintype "input"))
    )
    (net (code "37") (name "Net-(W28-DOUT)") (class "Default")
      (node (ref "W28") (pin "2") (pinfunction "DOUT_2") (pintype "output"))
      (node (ref "W29") (pin "4") (pinfunction "DIN_4") (pintype "input"))
    )
    (net (code "38") (name "Net-(W29-DOUT)") (class "Default")
      (node (ref "W29") (pin "2") (pinfunction "DOUT_2") (pintype "output"))
      (node (ref "W30") (pin "4") (pinfunction "DIN_4") (pintype "input"))
    )
    (net (code "39") (name "Net-(W30-DOUT)") (class "Default")
      (node (ref "W30") (pin "2") (pinfunction "DOUT_2") (pintype "output"))
      (node (ref "W31") (pin "4") (pinfunction "DIN_4") (pintype "input"))
    )
    (net (code "40") (name "Net-(W31-DOUT)") (class "Default")
      (node (ref "W31") (pin "2") (pinfunction "DOUT_2") (pintype "output"))
      (node (ref "W32") (pin "4") (pinfunction "DIN_4") (pintype "input"))
    )
    (net (code "41") (name "Net-(W32-DOUT)") (class "Default")
      (node (ref "W32") (pin "2") (pinfunction "DOUT_2") (pintype "output"))
      (node (ref "W33") (pin "4") (pinfunction "DIN_4") (pintype "input"))
    )
    (net (code "42") (name "Net-(W33-DOUT)") (class "Default")
      (node (ref "W33") (pin "2") (pinfunction "DOUT_2") (pintype "output"))
      (node (ref "W34") (pin "4") (pinfunction "DIN_4") (pintype "input"))
    )
    (net (code "43") (name "Net-(W34-DOUT)") (class "Default")
      (node (ref "W34") (pin "2") (pinfunction "DOUT_2") (pintype "output"))
      (node (ref "W35") (pin "4") (pinfunction "DIN_4") (pintype "input"))
    )
    (net (code "44") (name "Net-(W35-DOUT)") (class "Default")
      (node (ref "W35") (pin "2") (pinfunction "DOUT_2") (pintype "output"))
      (node (ref "W36") (pin "4") (pinfunction "DIN_4") (pintype "input"))
    )
    (net (code "45") (name "Net-(W36-DOUT)") (class "Default")
      (node (ref "W36") (pin "2") (pinfunction "DOUT_2") (pintype "output"))
      (node (ref "W37") (pin "4") (pinfunction "DIN_4") (pintype "input"))
    )
    (net (code "46") (name "Net-(W37-DOUT)") (class "Default")
      (node (ref "W37") (pin "2") (pinfunction "DOUT_2") (pintype "output"))
      (node (ref "W38") (pin "4") (pinfunction "DIN_4") (pintype "input"))
    )
    (net (code "47") (name "Net-(W38-DOUT)") (class "Default")
      (node (ref "W38") (pin "2") (pinfunction "DOUT_2") (pintype "output"))
      (node (ref "W39") (pin "4") (pinfunction "DIN_4") (pintype "input"))
    )
    (net (code "48") (name "Net-(W39-DOUT)") (class "Default")
      (node (ref "W39") (pin "2") (pinfunction "DOUT_2") (pintype "output"))
      (node (ref "W40") (pin "4") (pinfunction "DIN_4") (pintype "input"))
    )
    (net (code "49") (name "Net-(W40-DOUT)") (class "Default")
      (node (ref "W40") (pin "2") (pinfunction "DOUT_2") (pintype "output"))
      (node (ref "W41") (pin "4") (pinfunction "DIN_4") (pintype "input"))
    )
    (net (code "50") (name "Net-(W41-DOUT)") (class "Default")
      (node (ref "W41") (pin "2") (pinfunction "DOUT_2") (pintype "output"))
      (node (ref "W42") (pin "4") (pinfunction "DIN_4") (pintype "input"))
    )
    (net (code "51") (name "Net-(W42-DOUT)") (class "Default")
      (node (ref "W42") (pin "2") (pinfunction "DOUT_2") (pintype "output"))
      (node (ref "W43") (pin "4") (pinfunction "DIN_4") (pintype "input"))
    )
    (net (code "52") (name "Net-(W43-DOUT)") (class "Default")
      (node (ref "W43") (pin "2") (pinfunction "DOUT_2") (pintype "output"))
      (node (ref "W44") (pin "4") (pinfunction "DIN_4") (pintype "input"))
    )
    (net (code "53") (name "Net-(W44-DOUT)") (class "Default")
      (node (ref "W44") (pin "2") (pinfunction "DOUT_2") (pintype "output"))
      (node (ref "W45") (pin "4") (pinfunction "DIN_4") (pintype "input"))
    )
    (net (code "54") (name "Net-(W45-DOUT)") (class "Default")
      (node (ref "W45") (pin "2") (pinfunction "DOUT_2") (pintype "output"))
      (node (ref "W46") (pin "4") (pinfunction "DIN_4") (pintype "input"))
    )
    (net (code "55") (name "Net-(W46-DOUT)") (class "Default")
      (node (ref "W46") (pin "2") (pinfunction "DOUT_2") (pintype "output"))
      (node (ref "W47") (pin "4") (pinfunction "DIN_4") (pintype "input"))
    )
    (net (code "56") (name "Net-(W47-DOUT)") (class "Default")
      (node (ref "W47") (pin "2") (pinfunction "DOUT_2") (pintype "output"))
      (node (ref "W48") (pin "4") (pinfunction "DIN_4") (pintype "input"))
    )
    (net (code "57") (name "Net-(W48-DOUT)") (class "Default")
      (node (ref "W48") (pin "2") (pinfunction "DOUT_2") (pintype "output"))
      (node (ref "W49") (pin "4") (pinfunction "DIN_4") (pintype "input"))
    )
    (net (code "58") (name "Net-(W49-DOUT)") (class "Default")
      (node (ref "W49") (pin "2") (pinfunction "DOUT_2") (pintype "output"))
      (node (ref "W50") (pin "4") (pinfunction "DIN_4") (pintype "input"))
    )
    (net (code "59") (name "Net-(W50-DOUT)") (class "Default")
      (node (ref "W50") (pin "2") (pinfunction "DOUT_2") (pintype "output"))
      (node (ref "W51") (pin "4") (pinfunction "DIN_4") (pintype "input"))
    )
    (net (code "60") (name "Net-(W51-DOUT)") (class "Default")
      (node (ref "W51") (pin "2") (pinfunction "DOUT_2") (pintype "output"))
      (node (ref "W52") (pin "4") (pinfunction "DIN_4") (pintype "input"))
    )
    (net (code "61") (name "Net-(W52-DOUT)") (class "Default")
      (node (ref "W52") (pin "2") (pinfunction "DOUT_2") (pintype "output"))
      (node (ref "W53") (pin "4") (pinfunction "DIN_4") (pintype "input"))
    )
    (net (code "62") (name "Net-(W53-DOUT)") (class "Default")
      (node (ref "W53") (pin "2") (pinfunction "DOUT_2") (pintype "output"))
      (node (ref "W54") (pin "4") (pinfunction "DIN_4") (pintype "input"))
    )
    (net (code "63") (name "Net-(W54-DOUT)") (class "Default")
      (node (ref "W54") (pin "2") (pinfunction "DOUT_2") (pintype "output"))
      (node (ref "W55") (pin "4") (pinfunction "DIN_4") (pintype "input"))
    )
    (net (code "64") (name "Net-(W55-DOUT)") (class "Default")
      (node (ref "W55") (pin "2") (pinfunction "DOUT_2") (pintype "output"))
      (node (ref "W56") (pin "4") (pinfunction "DIN_4") (pintype "input"))
    )
    (net (code "65") (name "Net-(W56-DOUT)") (class "Default")
      (node (ref "W56") (pin "2") (pinfunction "DOUT_2") (pintype "output"))
      (node (ref "W57") (pin "4") (pinfunction "DIN_4") (pintype "input"))
    )
    (net (code "66") (name "Net-(W57-DOUT)") (class "Default")
      (node (ref "W57") (pin "2") (pinfunction "DOUT_2") (pintype "output"))
      (node (ref "W58") (pin "4") (pinfunction "DIN_4") (pintype "input"))
    )
    (net (code "67") (name "Net-(W58-DOUT)") (class "Default")
      (node (ref "W58") (pin "2") (pinfunction "DOUT_2") (pintype "output"))
      (node (ref "W59") (pin "4") (pinfunction "DIN_4") (pintype "input"))
    )
    (net (code "68") (name "Net-(W59-DOUT)") (class "Default")
      (node (ref "W59") (pin "2") (pinfunction "DOUT_2") (pintype "output"))
      (node (ref "W60") (pin "4") (pinfunction "DIN_4") (pintype "input"))
    )
    (net (code "69") (name "Net-(W60-DOUT)") (class "Default")
      (node (ref "W60") (pin "2") (pinfunction "DOUT_2") (pintype "output"))
      (node (ref "W61") (pin "4") (pinfunction "DIN_4") (pintype "input"))
    )
    (net (code "70") (name "Net-(W61-DOUT)") (class "Default")
      (node (ref "W61") (pin "2") (pinfunction "DOUT_2") (pintype "output"))
      (node (ref "W62") (pin "4") (pinfunction "DIN_4") (pintype "input"))
    )
    (net (code "71") (name "Net-(W62-DOUT)") (class "Default")
      (node (ref "W62") (pin "2") (pinfunction "DOUT_2") (pintype "output"))
      (node (ref "W63") (pin "4") (pinfunction "DIN_4") (pintype "input"))
    )
    (net (code "72") (name "Net-(W63-DOUT)") (class "Default")
      (node (ref "W63") (pin "2") (pinfunction "DOUT_2") (pintype "output"))
      (node (ref "W64") (pin "4") (pinfunction "DIN_4") (pintype "input"))
    )
    (net (code "73") (name "Net-(W64-DOUT)") (class "Default")
      (node (ref "W64") (pin "2") (pinfunction "DOUT_2") (pintype "output"))
      (node (ref "W65") (pin "4") (pinfunction "DIN_4") (pintype "input"))
    )
    (net (code "74") (name "Net-(W65-DOUT)") (class "Default")
      (node (ref "W65") (pin "2") (pinfunction "DOUT_2") (pintype "output"))
      (node (ref "W66") (pin "4") (pinfunction "DIN_4") (pintype "input"))
    )
    (net (code "75") (name "Net-(W66-DOUT)") (class "Default")
      (node (ref "W66") (pin "2") (pinfunction "DOUT_2") (pintype "output"))
      (node (ref "W67") (pin "4") (pinfunction "DIN_4") (pintype "input"))
    )
    (net (code "76") (name "Net-(W67-DOUT)") (class "Default")
      (node (ref "W67") (pin "2") (pinfunction "DOUT_2") (pintype "output"))
      (node (ref "W68") (pin "4") (pinfunction "DIN_4") (pintype "input"))
    )
    (net (code "77") (name "Net-(W68-DOUT)") (class "Default")
      (node (ref "W68") (pin "2") (pinfunction "DOUT_2") (pintype "output"))
      (node (ref "W69") (pin "4") (pinfunction "DIN_4") (pintype "input"))
    )
    (net (code "78") (name "Net-(W69-DOUT)") (class "Default")
      (node (ref "W69") (pin "2") (pinfunction "DOUT_2") (pintype "output"))
      (node (ref "W70") (pin "4") (pinfunction "DIN_4") (pintype "input"))
    )
    (net (code "79") (name "Net-(W70-DOUT)") (class "Default")
      (node (ref "W70") (pin "2") (pinfunction "DOUT_2") (pintype "output"))
      (node (ref "W71") (pin "4") (pinfunction "DIN_4") (pintype "input"))
    )
    (net (code "80") (name "Net-(W71-DOUT)") (class "Default")
      (node (ref "W71") (pin "2") (pinfunction "DOUT_2") (pintype "output"))
      (node (ref "W72") (pin "4") (pinfunction "DIN_4") (pintype "input"))
    )
    (net (code "81") (name "Net-(W72-DOUT)") (class "Default")
      (node (ref "W72") (pin "2") (pinfunction "DOUT_2") (pintype "output"))
      (node (ref "W73") (pin "4") (pinfunction "DIN_4") (pintype "input"))
    )
    (net (code "82") (name "Net-(W73-DOUT)") (class "Default")
      (node (ref "W73") (pin "2") (pinfunction "DOUT_2") (pintype "output"))
      (node (ref "W74") (pin "4") (pinfunction "DIN_4") (pintype "input"))
    )
    (net (code "83") (name "Net-(W74-DOUT)") (class "Default")
      (node (ref "W74") (pin "2") (pinfunction "DOUT_2") (pintype "output"))
      (node (ref "W75") (pin "4") (pinfunction "DIN_4") (pintype "input"))
    )
    (net (code "84") (name "Net-(W75-DOUT)") (class "Default")
      (node (ref "W75") (pin "2") (pinfunction "DOUT_2") (pintype "output"))
      (node (ref "W76") (pin "4") (pinfunction "DIN_4") (pintype "input"))
    )
    (net (code "85") (name "Net-(W76-DOUT)") (class "Default")
      (node (ref "W76") (pin "2") (pinfunction "DOUT_2") (pintype "output"))
      (node (ref "W77") (pin "4") (pinfunction "DIN_4") (pintype "input"))
    )
    (net (code "86") (name "Net-(W77-DOUT)") (class "Default")
      (node (ref "W77") (pin "2") (pinfunction "DOUT_2") (pintype "output"))
      (node (ref "W78") (pin "4") (pinfunction "DIN_4") (pintype "input"))
    )
    (net (code "87") (name "Net-(W78-DOUT)") (class "Default")
      (node (ref "W78") (pin "2") (pinfunction "DOUT_2") (pintype "output"))
      (node (ref "W79") (pin "4") (pinfunction "DIN_4") (pintype "input"))
    )
    (net (code "88") (name "Net-(W79-DOUT)") (class "Default")
      (node (ref "W79") (pin "2") (pinfunction "DOUT_2") (pintype "output"))
      (node (ref "W80") (pin "4") (pinfunction "DIN_4") (pintype "input"))
    )
    (net (code "89") (name "unconnected-(W80-DOUT-Pad2)") (class "Default")
      (node (ref "W80") (pin "2") (pinfunction "DOUT_2") (pintype "output"))
    )
  )
)
